# 12T_GAUGE_INPUT.net
KiCad netlist of a schematic drawn in EAGLE
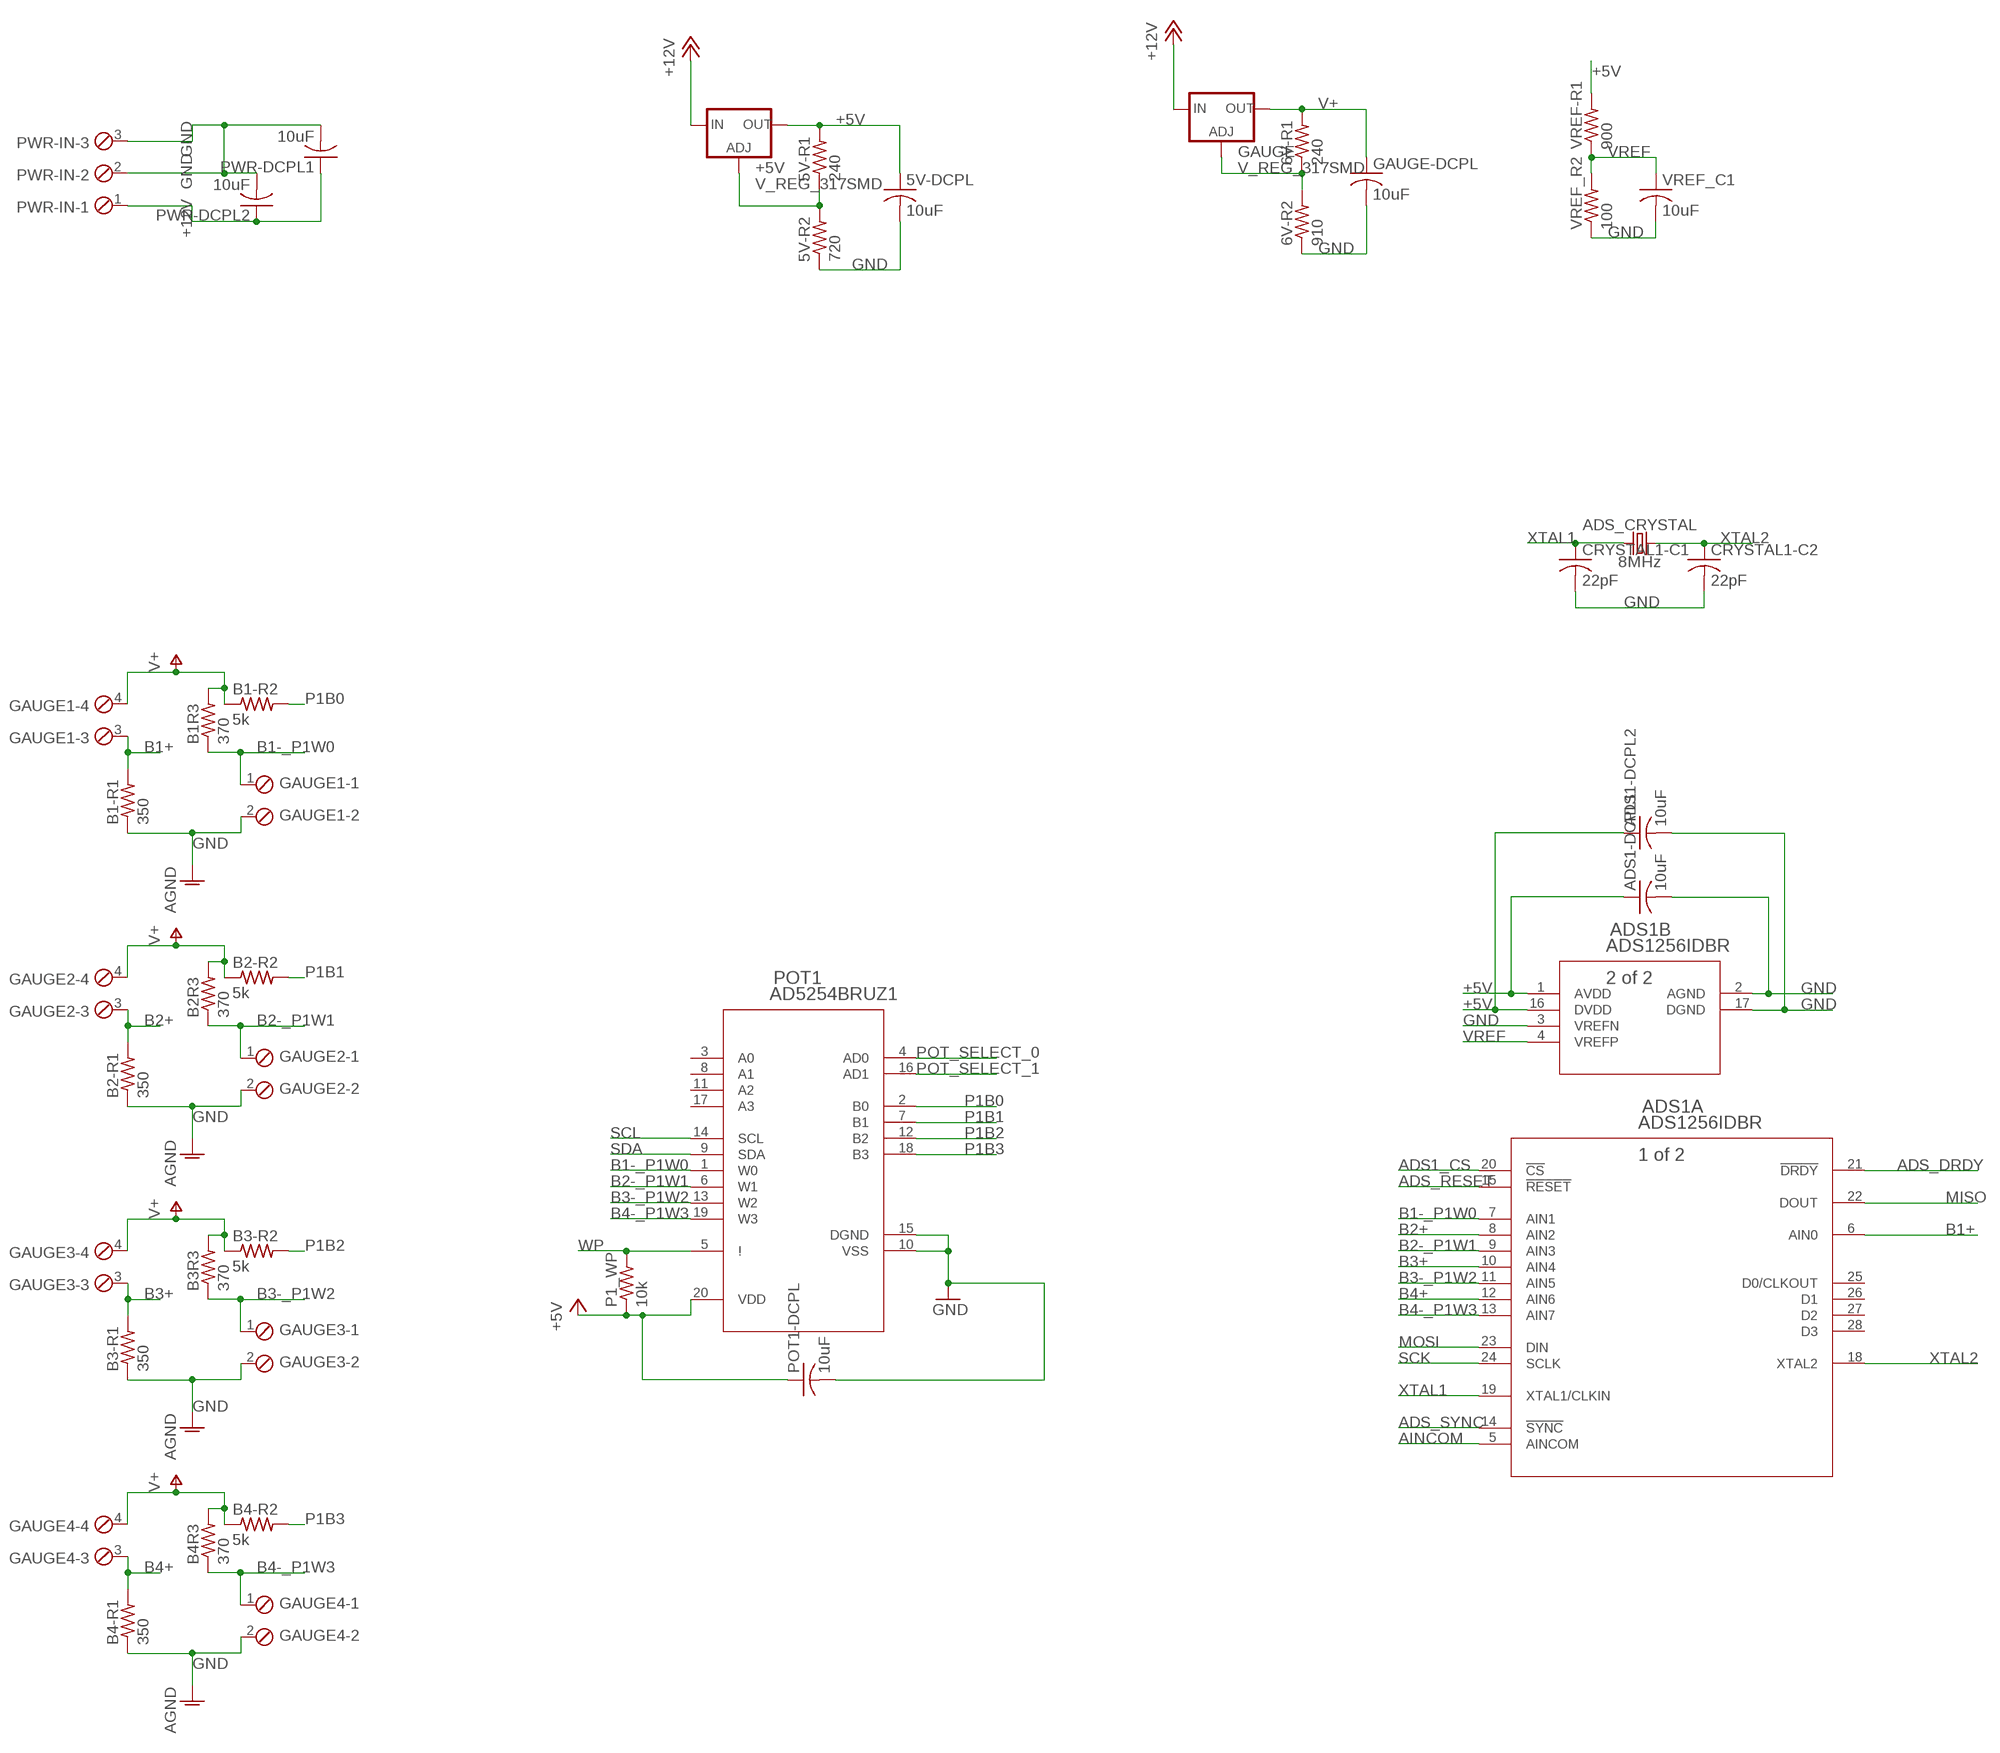
[diagram p0: schematic, sheet 1, part 1 of 3]
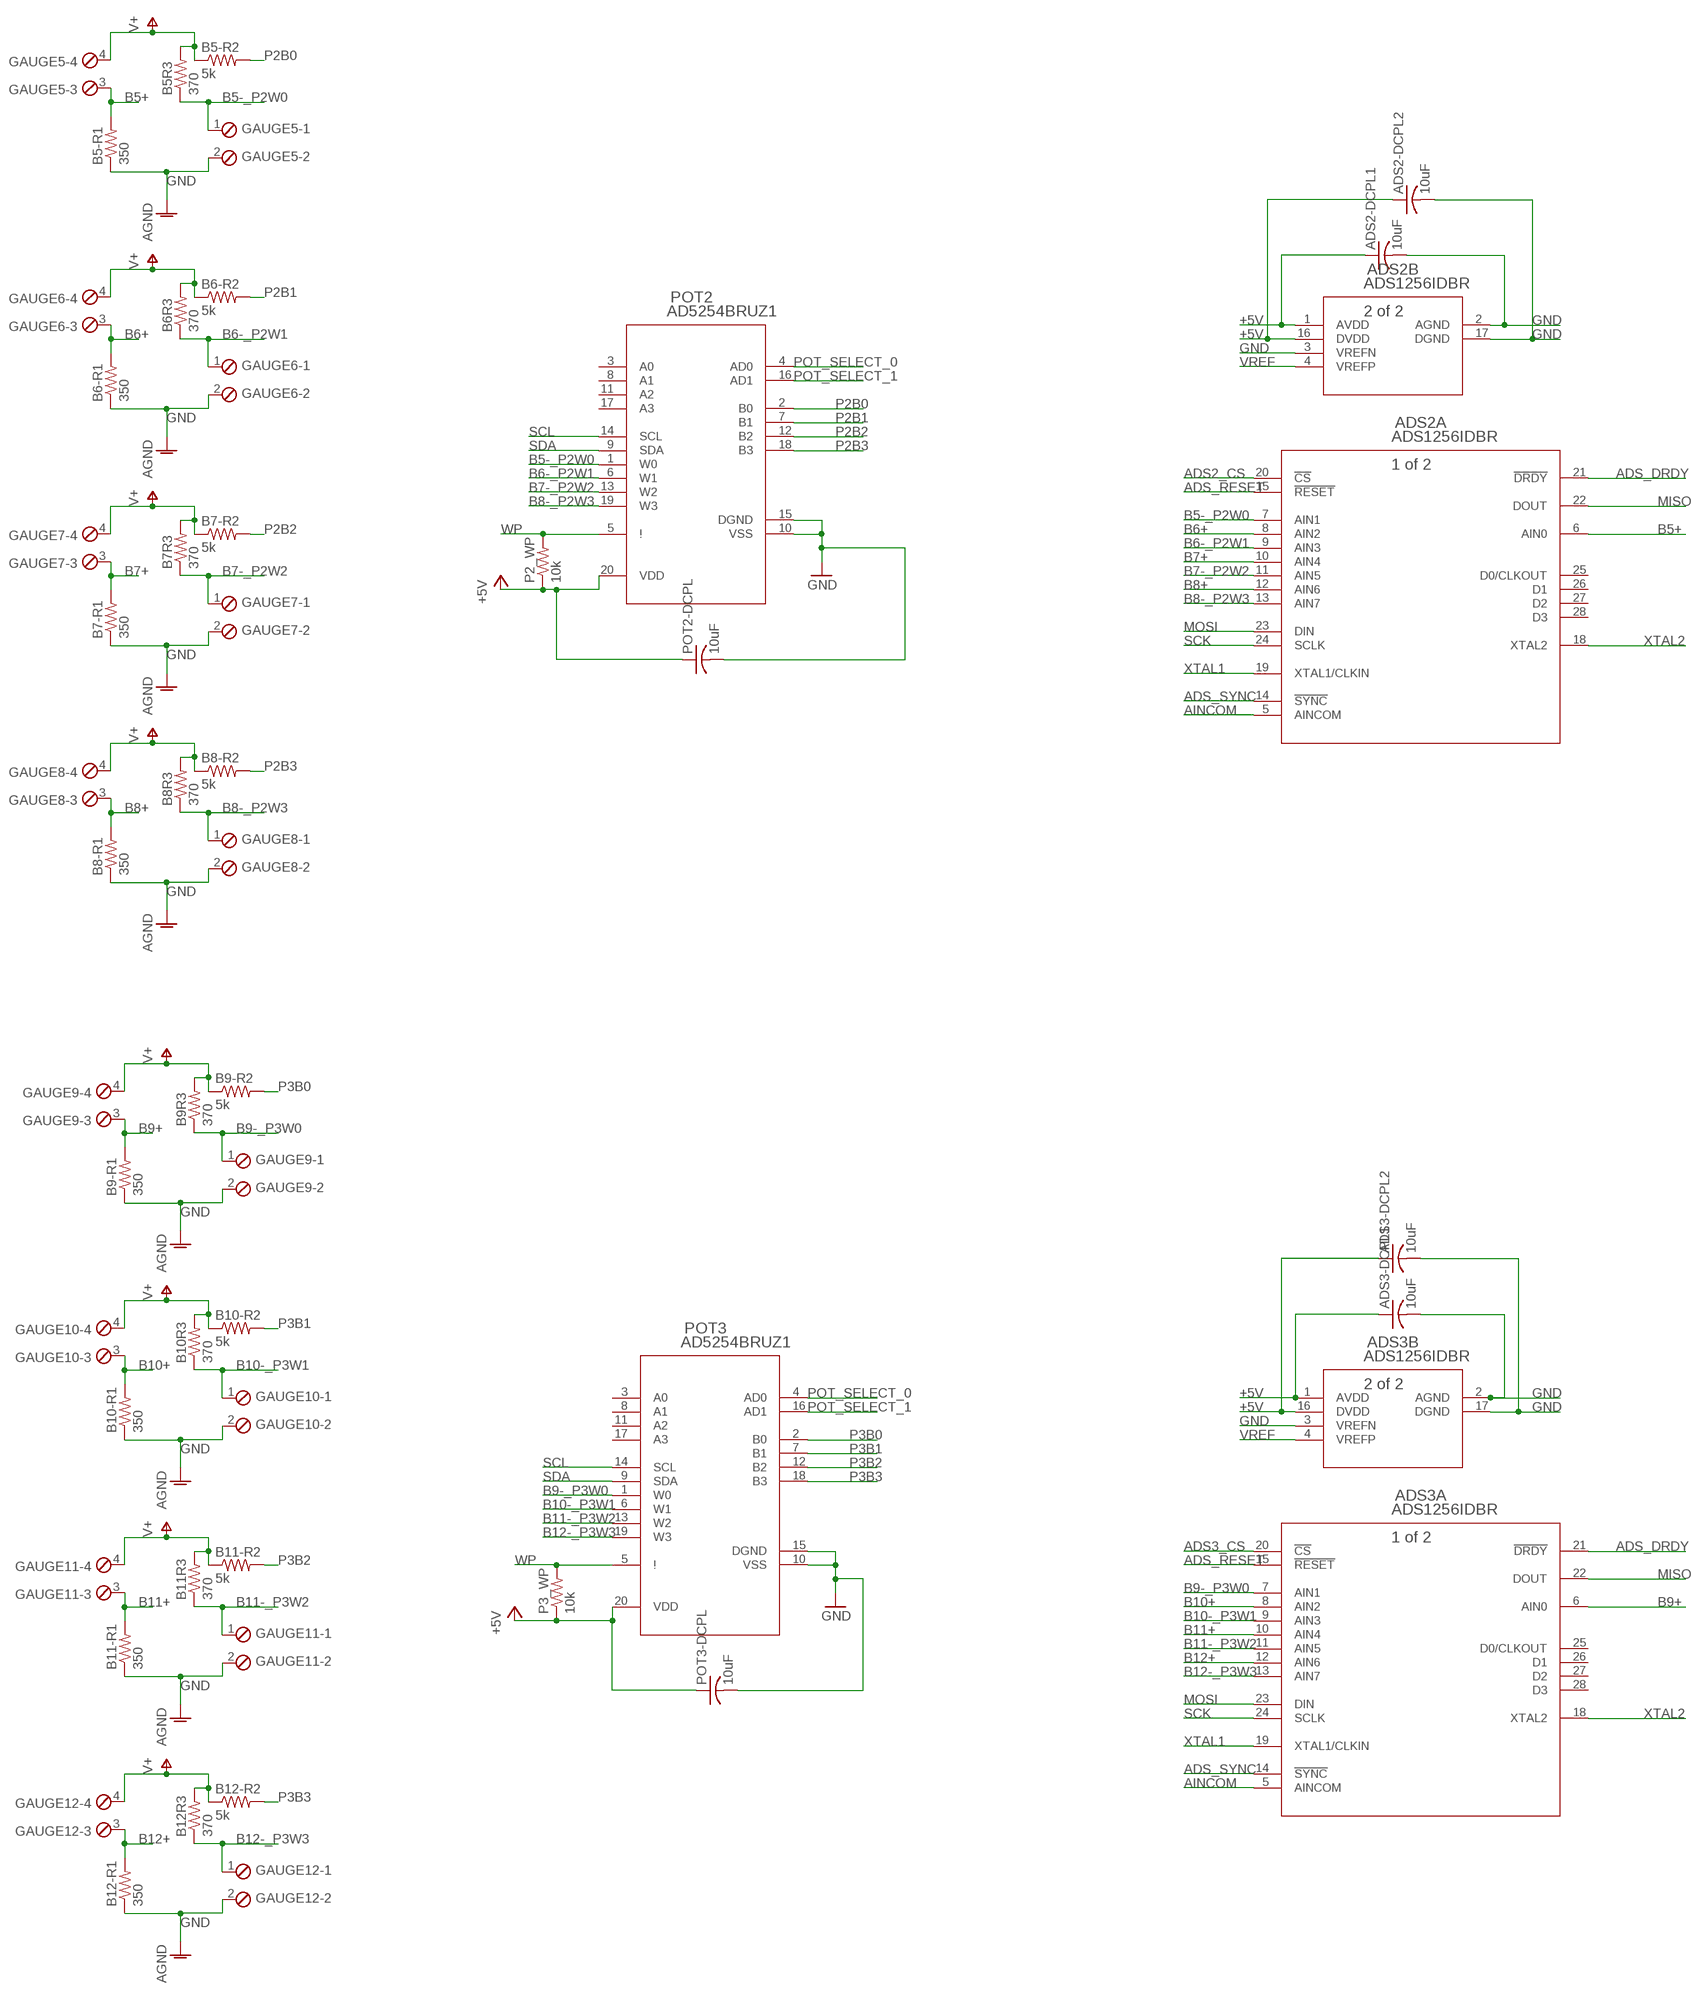
[diagram p1: schematic, sheet 1, part 2 of 3]
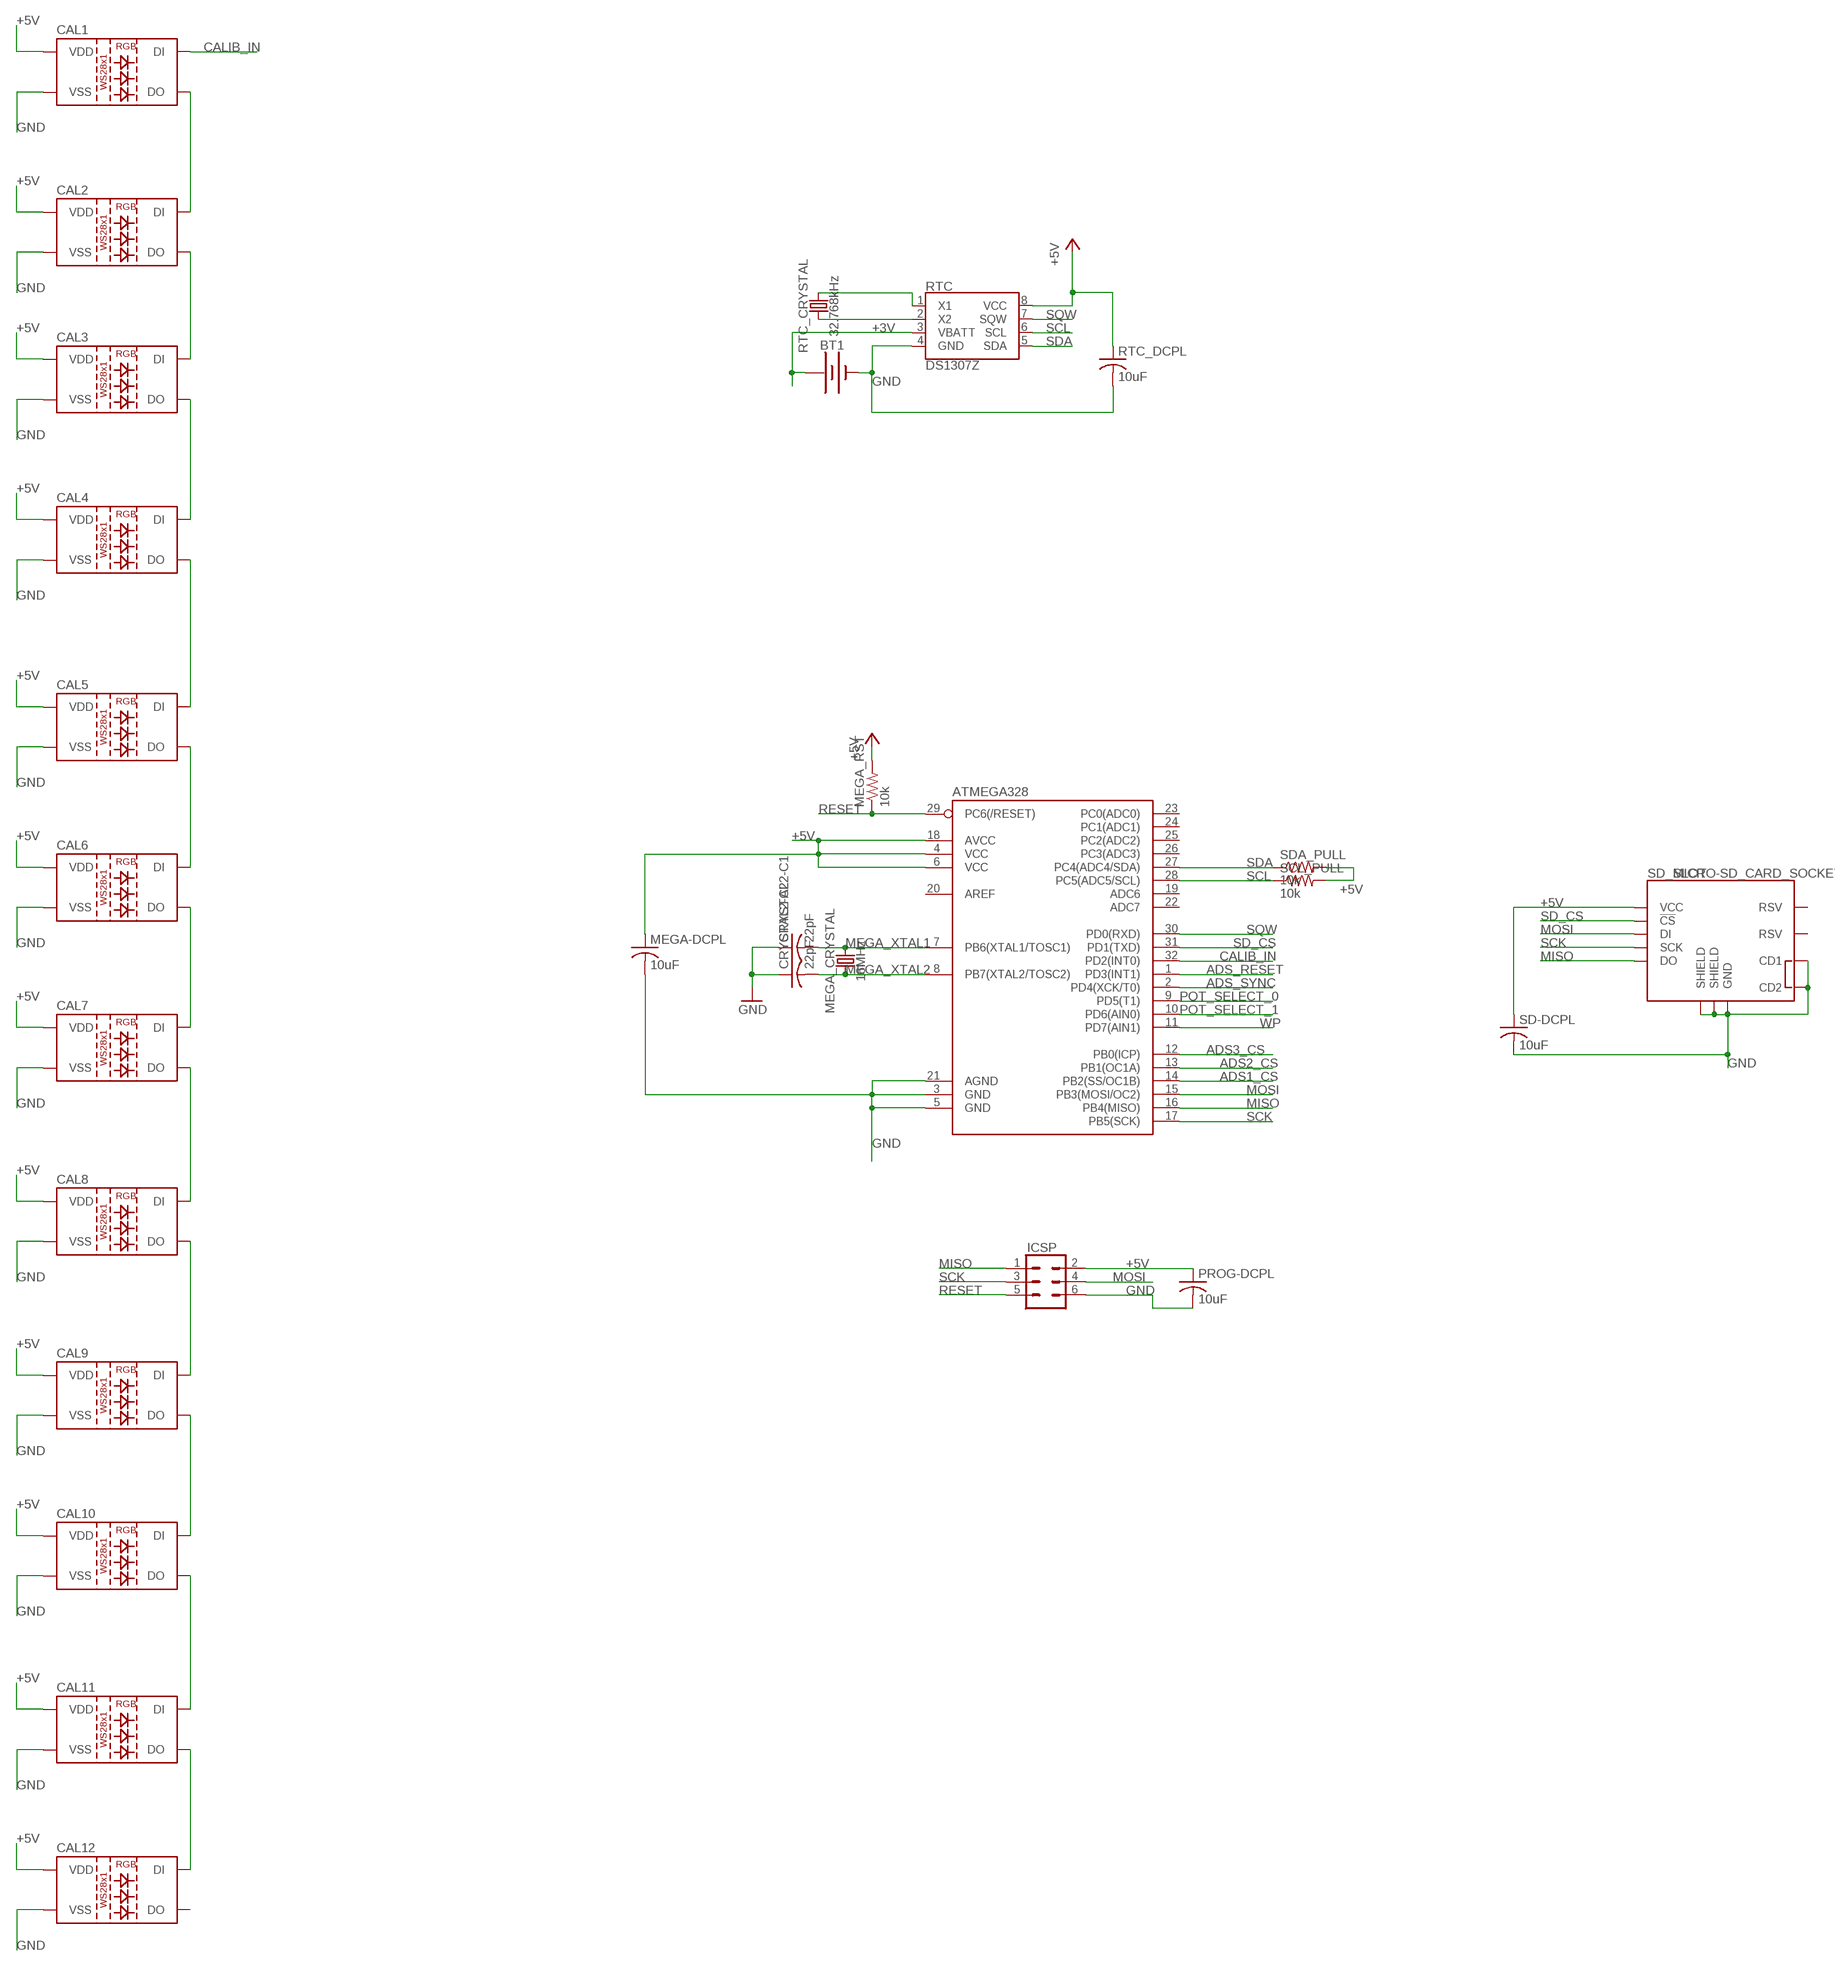
[diagram p2: schematic, sheet 1, part 3 of 3]

(export (version "E")
  (design (tool "Eeschema 10.0.6"))
  (components
    (comp (ref "+5V")
      (value "V_REG_317SMD")
      (footprint "eagle-import:SOT223")
      (libsource (lib "eagle-import") (part "V_REG_317SMD"))
    )
    (comp (ref "5V-DCPL")
      (value "10uF")
      (footprint "eagle-import:C1206")
      (libsource (lib "eagle-import") (part "C-USC1206"))
    )
    (comp (ref "5V-R1")
      (value "240")
      (footprint "eagle-import:R1206")
      (libsource (lib "eagle-import") (part "R-US_R1206"))
    )
    (comp (ref "5V-R2")
      (value "720")
      (footprint "eagle-import:R1206")
      (libsource (lib "eagle-import") (part "R-US_R1206"))
    )
    (comp (ref "6V-R1")
      (value "240")
      (footprint "eagle-import:R1206")
      (libsource (lib "eagle-import") (part "R-US_R1206"))
    )
    (comp (ref "6V-R2")
      (value "910")
      (footprint "eagle-import:R1206")
      (libsource (lib "eagle-import") (part "R-US_R1206"))
    )
    (comp (ref "ADS1")
      (value "ADS1256IDBR")
      (footprint "eagle-import:DB28")
      (libsource (lib "eagle-import") (part "ADS1256IDBR"))
    )
    (comp (ref "ADS1-DCPL1")
      (value "10uF")
      (footprint "eagle-import:C1206")
      (libsource (lib "eagle-import") (part "C-USC1206"))
    )
    (comp (ref "ADS1-DCPL2")
      (value "10uF")
      (footprint "eagle-import:C1206")
      (libsource (lib "eagle-import") (part "C-USC1206"))
    )
    (comp (ref "ADS2")
      (value "ADS1256IDBR")
      (footprint "eagle-import:DB28")
      (libsource (lib "eagle-import") (part "ADS1256IDBR"))
    )
    (comp (ref "ADS2-DCPL1")
      (value "10uF")
      (footprint "eagle-import:C1206")
      (libsource (lib "eagle-import") (part "C-USC1206"))
    )
    (comp (ref "ADS2-DCPL2")
      (value "10uF")
      (footprint "eagle-import:C1206")
      (libsource (lib "eagle-import") (part "C-USC1206"))
    )
    (comp (ref "ADS3")
      (value "ADS1256IDBR")
      (footprint "eagle-import:DB28")
      (libsource (lib "eagle-import") (part "ADS1256IDBR"))
    )
    (comp (ref "ADS3-DCPL1")
      (value "10uF")
      (footprint "eagle-import:C1206")
      (libsource (lib "eagle-import") (part "C-USC1206"))
    )
    (comp (ref "ADS3-DCPL2")
      (value "10uF")
      (footprint "eagle-import:C1206")
      (libsource (lib "eagle-import") (part "C-USC1206"))
    )
    (comp (ref "ADS_CRYSTAL")
      (value "8MHz")
      (footprint "eagle-import:CRYSTAL-SMD-5X3.2-4PAD")
      (libsource (lib "eagle-import") (part "CRYSTAL-8MHZSMD-5X3.2"))
    )
    (comp (ref "ATMEGA328")
      (value "ATMEGA328P_TQFP")
      (footprint "eagle-import:TQFP32-08")
      (libsource (lib "eagle-import") (part "ATMEGA328P_TQFP"))
    )
    (comp (ref "B1-R1")
      (value "350")
      (footprint "eagle-import:R1206")
      (libsource (lib "eagle-import") (part "R-US_R1206"))
    )
    (comp (ref "B1-R2")
      (value "5k")
      (footprint "eagle-import:R1206")
      (libsource (lib "eagle-import") (part "R-US_R1206"))
    )
    (comp (ref "B1R3")
      (value "370")
      (footprint "eagle-import:R1206")
      (libsource (lib "eagle-import") (part "R-US_R1206"))
    )
    (comp (ref "B2-R1")
      (value "350")
      (footprint "eagle-import:R1206")
      (libsource (lib "eagle-import") (part "R-US_R1206"))
    )
    (comp (ref "B2-R2")
      (value "5k")
      (footprint "eagle-import:R1206")
      (libsource (lib "eagle-import") (part "R-US_R1206"))
    )
    (comp (ref "B2R3")
      (value "370")
      (footprint "eagle-import:R1206")
      (libsource (lib "eagle-import") (part "R-US_R1206"))
    )
    (comp (ref "B3-R1")
      (value "350")
      (footprint "eagle-import:R1206")
      (libsource (lib "eagle-import") (part "R-US_R1206"))
    )
    (comp (ref "B3-R2")
      (value "5k")
      (footprint "eagle-import:R1206")
      (libsource (lib "eagle-import") (part "R-US_R1206"))
    )
    (comp (ref "B3R3")
      (value "370")
      (footprint "eagle-import:R1206")
      (libsource (lib "eagle-import") (part "R-US_R1206"))
    )
    (comp (ref "B4-R1")
      (value "350")
      (footprint "eagle-import:R1206")
      (libsource (lib "eagle-import") (part "R-US_R1206"))
    )
    (comp (ref "B4-R2")
      (value "5k")
      (footprint "eagle-import:R1206")
      (libsource (lib "eagle-import") (part "R-US_R1206"))
    )
    (comp (ref "B4R3")
      (value "370")
      (footprint "eagle-import:R1206")
      (libsource (lib "eagle-import") (part "R-US_R1206"))
    )
    (comp (ref "B5-R1")
      (value "350")
      (footprint "eagle-import:R1206")
      (libsource (lib "eagle-import") (part "R-US_R1206"))
    )
    (comp (ref "B5-R2")
      (value "5k")
      (footprint "eagle-import:R1206")
      (libsource (lib "eagle-import") (part "R-US_R1206"))
    )
    (comp (ref "B5R3")
      (value "370")
      (footprint "eagle-import:R1206")
      (libsource (lib "eagle-import") (part "R-US_R1206"))
    )
    (comp (ref "B6-R1")
      (value "350")
      (footprint "eagle-import:R1206")
      (libsource (lib "eagle-import") (part "R-US_R1206"))
    )
    (comp (ref "B6-R2")
      (value "5k")
      (footprint "eagle-import:R1206")
      (libsource (lib "eagle-import") (part "R-US_R1206"))
    )
    (comp (ref "B6R3")
      (value "370")
      (footprint "eagle-import:R1206")
      (libsource (lib "eagle-import") (part "R-US_R1206"))
    )
    (comp (ref "B7-R1")
      (value "350")
      (footprint "eagle-import:R1206")
      (libsource (lib "eagle-import") (part "R-US_R1206"))
    )
    (comp (ref "B7-R2")
      (value "5k")
      (footprint "eagle-import:R1206")
      (libsource (lib "eagle-import") (part "R-US_R1206"))
    )
    (comp (ref "B7R3")
      (value "370")
      (footprint "eagle-import:R1206")
      (libsource (lib "eagle-import") (part "R-US_R1206"))
    )
    (comp (ref "B8-R1")
      (value "350")
      (footprint "eagle-import:R1206")
      (libsource (lib "eagle-import") (part "R-US_R1206"))
    )
    (comp (ref "B8-R2")
      (value "5k")
      (footprint "eagle-import:R1206")
      (libsource (lib "eagle-import") (part "R-US_R1206"))
    )
    (comp (ref "B8R3")
      (value "370")
      (footprint "eagle-import:R1206")
      (libsource (lib "eagle-import") (part "R-US_R1206"))
    )
    (comp (ref "B9-R1")
      (value "350")
      (footprint "eagle-import:R1206")
      (libsource (lib "eagle-import") (part "R-US_R1206"))
    )
    (comp (ref "B9-R2")
      (value "5k")
      (footprint "eagle-import:R1206")
      (libsource (lib "eagle-import") (part "R-US_R1206"))
    )
    (comp (ref "B9R3")
      (value "370")
      (footprint "eagle-import:R1206")
      (libsource (lib "eagle-import") (part "R-US_R1206"))
    )
    (comp (ref "B10-R1")
      (value "350")
      (footprint "eagle-import:R1206")
      (libsource (lib "eagle-import") (part "R-US_R1206"))
    )
    (comp (ref "B10-R2")
      (value "5k")
      (footprint "eagle-import:R1206")
      (libsource (lib "eagle-import") (part "R-US_R1206"))
    )
    (comp (ref "B10R3")
      (value "370")
      (footprint "eagle-import:R1206")
      (libsource (lib "eagle-import") (part "R-US_R1206"))
    )
    (comp (ref "B11-R1")
      (value "350")
      (footprint "eagle-import:R1206")
      (libsource (lib "eagle-import") (part "R-US_R1206"))
    )
    (comp (ref "B11-R2")
      (value "5k")
      (footprint "eagle-import:R1206")
      (libsource (lib "eagle-import") (part "R-US_R1206"))
    )
    (comp (ref "B11R3")
      (value "370")
      (footprint "eagle-import:R1206")
      (libsource (lib "eagle-import") (part "R-US_R1206"))
    )
    (comp (ref "B12-R1")
      (value "350")
      (footprint "eagle-import:R1206")
      (libsource (lib "eagle-import") (part "R-US_R1206"))
    )
    (comp (ref "B12-R2")
      (value "5k")
      (footprint "eagle-import:R1206")
      (libsource (lib "eagle-import") (part "R-US_R1206"))
    )
    (comp (ref "B12R3")
      (value "370")
      (footprint "eagle-import:R1206")
      (libsource (lib "eagle-import") (part "R-US_R1206"))
    )
    (comp (ref "BT1")
      (value "BATTERY-12MM_SMD")
      (footprint "eagle-import:BATTCON_12MM")
      (libsource (lib "eagle-import") (part "BATTERY-12MM_SMD"))
    )
    (comp (ref "CAL1")
      (value "WS2812\"")
      (footprint "eagle-import:LED-TRICOLOR-5050-IC")
      (libsource (lib "eagle-import") (part "WS2812{dblquote}"))
    )
    (comp (ref "CAL2")
      (value "WS2812\"")
      (footprint "eagle-import:LED-TRICOLOR-5050-IC")
      (libsource (lib "eagle-import") (part "WS2812{dblquote}"))
    )
    (comp (ref "CAL3")
      (value "WS2812\"")
      (footprint "eagle-import:LED-TRICOLOR-5050-IC")
      (libsource (lib "eagle-import") (part "WS2812{dblquote}"))
    )
    (comp (ref "CAL4")
      (value "WS2812\"")
      (footprint "eagle-import:LED-TRICOLOR-5050-IC")
      (libsource (lib "eagle-import") (part "WS2812{dblquote}"))
    )
    (comp (ref "CAL5")
      (value "WS2812\"")
      (footprint "eagle-import:LED-TRICOLOR-5050-IC")
      (libsource (lib "eagle-import") (part "WS2812{dblquote}"))
    )
    (comp (ref "CAL6")
      (value "WS2812\"")
      (footprint "eagle-import:LED-TRICOLOR-5050-IC")
      (libsource (lib "eagle-import") (part "WS2812{dblquote}"))
    )
    (comp (ref "CAL7")
      (value "WS2812\"")
      (footprint "eagle-import:LED-TRICOLOR-5050-IC")
      (libsource (lib "eagle-import") (part "WS2812{dblquote}"))
    )
    (comp (ref "CAL8")
      (value "WS2812\"")
      (footprint "eagle-import:LED-TRICOLOR-5050-IC")
      (libsource (lib "eagle-import") (part "WS2812{dblquote}"))
    )
    (comp (ref "CAL9")
      (value "WS2812\"")
      (footprint "eagle-import:LED-TRICOLOR-5050-IC")
      (libsource (lib "eagle-import") (part "WS2812{dblquote}"))
    )
    (comp (ref "CAL10")
      (value "WS2812\"")
      (footprint "eagle-import:LED-TRICOLOR-5050-IC")
      (libsource (lib "eagle-import") (part "WS2812{dblquote}"))
    )
    (comp (ref "CAL11")
      (value "WS2812\"")
      (footprint "eagle-import:LED-TRICOLOR-5050-IC")
      (libsource (lib "eagle-import") (part "WS2812{dblquote}"))
    )
    (comp (ref "CAL12")
      (value "WS2812\"")
      (footprint "eagle-import:LED-TRICOLOR-5050-IC")
      (libsource (lib "eagle-import") (part "WS2812{dblquote}"))
    )
    (comp (ref "CRYSTAL1-C1")
      (value "22pF")
      (footprint "eagle-import:C1206")
      (libsource (lib "eagle-import") (part "C-USC1206"))
    )
    (comp (ref "CRYSTAL1-C2")
      (value "22pF")
      (footprint "eagle-import:C1206")
      (libsource (lib "eagle-import") (part "C-USC1206"))
    )
    (comp (ref "CRYSTAL2-C1")
      (value "22pF")
      (footprint "eagle-import:C1206")
      (libsource (lib "eagle-import") (part "C-USC1206"))
    )
    (comp (ref "CRYSTAL2-C2")
      (value "22pF")
      (footprint "eagle-import:C1206")
      (libsource (lib "eagle-import") (part "C-USC1206"))
    )
    (comp (ref "GAUGE")
      (value "V_REG_317SMD")
      (footprint "eagle-import:SOT223")
      (libsource (lib "eagle-import") (part "V_REG_317SMD"))
    )
    (comp (ref "GAUGE-DCPL")
      (value "10uF")
      (footprint "eagle-import:C1206")
      (libsource (lib "eagle-import") (part "C-USC1206"))
    )
    (comp (ref "GAUGE1")
      (value "MPT4")
      (footprint "eagle-import:4POL254")
      (libsource (lib "eagle-import") (part "MPT4"))
    )
    (comp (ref "GAUGE2")
      (value "MPT4")
      (footprint "eagle-import:4POL254")
      (libsource (lib "eagle-import") (part "MPT4"))
    )
    (comp (ref "GAUGE3")
      (value "MPT4")
      (footprint "eagle-import:4POL254")
      (libsource (lib "eagle-import") (part "MPT4"))
    )
    (comp (ref "GAUGE4")
      (value "MPT4")
      (footprint "eagle-import:4POL254")
      (libsource (lib "eagle-import") (part "MPT4"))
    )
    (comp (ref "GAUGE5")
      (value "MPT4")
      (footprint "eagle-import:4POL254")
      (libsource (lib "eagle-import") (part "MPT4"))
    )
    (comp (ref "GAUGE6")
      (value "MPT4")
      (footprint "eagle-import:4POL254")
      (libsource (lib "eagle-import") (part "MPT4"))
    )
    (comp (ref "GAUGE7")
      (value "MPT4")
      (footprint "eagle-import:4POL254")
      (libsource (lib "eagle-import") (part "MPT4"))
    )
    (comp (ref "GAUGE8")
      (value "MPT4")
      (footprint "eagle-import:4POL254")
      (libsource (lib "eagle-import") (part "MPT4"))
    )
    (comp (ref "GAUGE9")
      (value "MPT4")
      (footprint "eagle-import:4POL254")
      (libsource (lib "eagle-import") (part "MPT4"))
    )
    (comp (ref "GAUGE10")
      (value "MPT4")
      (footprint "eagle-import:4POL254")
      (libsource (lib "eagle-import") (part "MPT4"))
    )
    (comp (ref "GAUGE11")
      (value "MPT4")
      (footprint "eagle-import:4POL254")
      (libsource (lib "eagle-import") (part "MPT4"))
    )
    (comp (ref "GAUGE12")
      (value "MPT4")
      (footprint "eagle-import:4POL254")
      (libsource (lib "eagle-import") (part "MPT4"))
    )
    (comp (ref "ICSP")
      (value "CONN_03X2FEMALE_SMD")
      (footprint "eagle-import:2X3_SMD")
      (libsource (lib "eagle-import") (part "CONN_03X2FEMALE_SMD"))
    )
    (comp (ref "MEGA-DCPL")
      (value "10uF")
      (footprint "eagle-import:C1206")
      (libsource (lib "eagle-import") (part "C-USC1206"))
    )
    (comp (ref "MEGA_CRYSTAL")
      (value "16MHz")
      (footprint "eagle-import:CRYSTAL-SMD-5X3.2-4PAD")
      (libsource (lib "eagle-import") (part "CRYSTAL-16MHZSMD-5X3.2"))
    )
    (comp (ref "MEGA_RST")
      (value "10k")
      (footprint "eagle-import:R1206")
      (libsource (lib "eagle-import") (part "R-US_R1206"))
    )
    (comp (ref "P1_WP")
      (value "10k")
      (footprint "eagle-import:R1206")
      (libsource (lib "eagle-import") (part "R-US_R1206"))
    )
    (comp (ref "P2_WP")
      (value "10k")
      (footprint "eagle-import:R1206")
      (libsource (lib "eagle-import") (part "R-US_R1206"))
    )
    (comp (ref "P3_WP")
      (value "10k")
      (footprint "eagle-import:R1206")
      (libsource (lib "eagle-import") (part "R-US_R1206"))
    )
    (comp (ref "POT1")
      (value "AD5254BRUZ1")
      (footprint "eagle-import:RU_20")
      (libsource (lib "eagle-import") (part "AD5254BRUZ1"))
    )
    (comp (ref "POT1-DCPL")
      (value "10uF")
      (footprint "eagle-import:C1206")
      (libsource (lib "eagle-import") (part "C-USC1206"))
    )
    (comp (ref "POT2")
      (value "AD5254BRUZ1")
      (footprint "eagle-import:RU_20")
      (libsource (lib "eagle-import") (part "AD5254BRUZ1"))
    )
    (comp (ref "POT2-DCPL")
      (value "10uF")
      (footprint "eagle-import:C1206")
      (libsource (lib "eagle-import") (part "C-USC1206"))
    )
    (comp (ref "POT3")
      (value "AD5254BRUZ1")
      (footprint "eagle-import:RU_20")
      (libsource (lib "eagle-import") (part "AD5254BRUZ1"))
    )
    (comp (ref "POT3-DCPL")
      (value "10uF")
      (footprint "eagle-import:C1206")
      (libsource (lib "eagle-import") (part "C-USC1206"))
    )
    (comp (ref "PROG-DCPL")
      (value "10uF")
      (footprint "eagle-import:C1206")
      (libsource (lib "eagle-import") (part "C-USC1206"))
    )
    (comp (ref "PWR-DCPL1")
      (value "10uF")
      (footprint "eagle-import:C1206")
      (libsource (lib "eagle-import") (part "C-USC1206"))
    )
    (comp (ref "PWR-DCPL2")
      (value "10uF")
      (footprint "eagle-import:C1206")
      (libsource (lib "eagle-import") (part "C-USC1206"))
    )
    (comp (ref "PWR-IN")
      (value "MPT3")
      (footprint "eagle-import:3POL254")
      (libsource (lib "eagle-import") (part "MPT3"))
    )
    (comp (ref "RTC")
      (value "DS1307Z")
      (footprint "eagle-import:SO08-0.15")
      (libsource (lib "eagle-import") (part "DS1307Z"))
    )
    (comp (ref "RTC_CRYSTAL")
      (value "32.768kHz")
      (footprint "eagle-import:CRYSTAL-SMD-3.2X1.5MM")
      (libsource (lib "eagle-import") (part "CRYSTAL-32.768KHZSMD-3.2X1.5"))
    )
    (comp (ref "RTC_DCPL")
      (value "10uF")
      (footprint "eagle-import:C1206")
      (libsource (lib "eagle-import") (part "C-USC1206"))
    )
    (comp (ref "SCL_PULL")
      (value "10k")
      (footprint "eagle-import:R1206")
      (libsource (lib "eagle-import") (part "R-US_R1206"))
    )
    (comp (ref "SD-DCPL")
      (value "10uF")
      (footprint "eagle-import:C1206")
      (libsource (lib "eagle-import") (part "C-USC1206"))
    )
    (comp (ref "SDA_PULL")
      (value "10k")
      (footprint "eagle-import:R1206")
      (libsource (lib "eagle-import") (part "R-US_R1206"))
    )
    (comp (ref "SD_SLOT")
      (value "MICRO-SD_CARD_SOCKET")
      (footprint "eagle-import:MICRO-SD-SOCKET")
      (libsource (lib "eagle-import") (part "MICRO-SD_CARD_SOCKET"))
    )
    (comp (ref "VREF-R1")
      (value "900")
      (footprint "eagle-import:R1206")
      (libsource (lib "eagle-import") (part "R-US_R1206"))
    )
    (comp (ref "VREF_C1")
      (value "10uF")
      (footprint "eagle-import:C1206")
      (libsource (lib "eagle-import") (part "C-USC1206"))
    )
    (comp (ref "VREF_R2")
      (value "100")
      (footprint "eagle-import:R1206")
      (libsource (lib "eagle-import") (part "R-US_R1206"))
    )
  )
  (nets
    (net (code "1") (name "+5V") (class "Default")
      (node (ref "+5V") (pin "2") (pinfunction "OUT_2") (pintype "output"))
      (node (ref "5V-DCPL") (pin "1") (pinfunction "1_1") (pintype "passive"))
      (node (ref "5V-R1") (pin "2") (pinfunction "2_2") (pintype "passive"))
      (node (ref "ADS1") (pin "1") (pinfunction "AVDD_1") (pintype "passive"))
      (node (ref "ADS1") (pin "16") (pinfunction "DVDD_16") (pintype "power_in"))
      (node (ref "ADS1-DCPL1") (pin "1") (pinfunction "1_1") (pintype "passive"))
      (node (ref "ADS1-DCPL2") (pin "1") (pinfunction "1_1") (pintype "passive"))
      (node (ref "ADS2") (pin "1") (pinfunction "AVDD_1") (pintype "passive"))
      (node (ref "ADS2") (pin "16") (pinfunction "DVDD_16") (pintype "power_in"))
      (node (ref "ADS2-DCPL1") (pin "1") (pinfunction "1_1") (pintype "passive"))
      (node (ref "ADS2-DCPL2") (pin "1") (pinfunction "1_1") (pintype "passive"))
      (node (ref "ADS3") (pin "1") (pinfunction "AVDD_1") (pintype "passive"))
      (node (ref "ADS3") (pin "16") (pinfunction "DVDD_16") (pintype "power_in"))
      (node (ref "ADS3-DCPL1") (pin "1") (pinfunction "1_1") (pintype "passive"))
      (node (ref "ADS3-DCPL2") (pin "1") (pinfunction "1_1") (pintype "passive"))
      (node (ref "ATMEGA328") (pin "18") (pinfunction "AVCC_18") (pintype "bidirectional"))
      (node (ref "ATMEGA328") (pin "4") (pinfunction "VCC_4") (pintype "bidirectional"))
      (node (ref "ATMEGA328") (pin "6") (pinfunction "VCC_6") (pintype "bidirectional"))
      (node (ref "CAL1") (pin "3") (pinfunction "VDD_3") (pintype "bidirectional"))
      (node (ref "CAL1") (pin "5") (pinfunction "VDD_5") (pintype "bidirectional"))
      (node (ref "CAL10") (pin "3") (pinfunction "VDD_3") (pintype "bidirectional"))
      (node (ref "CAL10") (pin "5") (pinfunction "VDD_5") (pintype "bidirectional"))
      (node (ref "CAL11") (pin "3") (pinfunction "VDD_3") (pintype "bidirectional"))
      (node (ref "CAL11") (pin "5") (pinfunction "VDD_5") (pintype "bidirectional"))
      (node (ref "CAL12") (pin "3") (pinfunction "VDD_3") (pintype "bidirectional"))
      (node (ref "CAL12") (pin "5") (pinfunction "VDD_5") (pintype "bidirectional"))
      (node (ref "CAL2") (pin "3") (pinfunction "VDD_3") (pintype "bidirectional"))
      (node (ref "CAL2") (pin "5") (pinfunction "VDD_5") (pintype "bidirectional"))
      (node (ref "CAL3") (pin "3") (pinfunction "VDD_3") (pintype "bidirectional"))
      (node (ref "CAL3") (pin "5") (pinfunction "VDD_5") (pintype "bidirectional"))
      (node (ref "CAL4") (pin "3") (pinfunction "VDD_3") (pintype "bidirectional"))
      (node (ref "CAL4") (pin "5") (pinfunction "VDD_5") (pintype "bidirectional"))
      (node (ref "CAL5") (pin "3") (pinfunction "VDD_3") (pintype "bidirectional"))
      (node (ref "CAL5") (pin "5") (pinfunction "VDD_5") (pintype "bidirectional"))
      (node (ref "CAL6") (pin "3") (pinfunction "VDD_3") (pintype "bidirectional"))
      (node (ref "CAL6") (pin "5") (pinfunction "VDD_5") (pintype "bidirectional"))
      (node (ref "CAL7") (pin "3") (pinfunction "VDD_3") (pintype "bidirectional"))
      (node (ref "CAL7") (pin "5") (pinfunction "VDD_5") (pintype "bidirectional"))
      (node (ref "CAL8") (pin "3") (pinfunction "VDD_3") (pintype "bidirectional"))
      (node (ref "CAL8") (pin "5") (pinfunction "VDD_5") (pintype "bidirectional"))
      (node (ref "CAL9") (pin "3") (pinfunction "VDD_3") (pintype "bidirectional"))
      (node (ref "CAL9") (pin "5") (pinfunction "VDD_5") (pintype "bidirectional"))
      (node (ref "ICSP") (pin "2") (pinfunction "2_2") (pintype "bidirectional"))
      (node (ref "MEGA-DCPL") (pin "1") (pinfunction "1_1") (pintype "passive"))
      (node (ref "MEGA_RST") (pin "2") (pinfunction "2_2") (pintype "passive"))
      (node (ref "P1_WP") (pin "1") (pinfunction "1_1") (pintype "passive"))
      (node (ref "P2_WP") (pin "1") (pinfunction "1_1") (pintype "passive"))
      (node (ref "P3_WP") (pin "1") (pinfunction "1_1") (pintype "passive"))
      (node (ref "POT1") (pin "20") (pinfunction "VDD_20") (pintype "power_in"))
      (node (ref "POT1-DCPL") (pin "1") (pinfunction "1_1") (pintype "passive"))
      (node (ref "POT2") (pin "20") (pinfunction "VDD_20") (pintype "power_in"))
      (node (ref "POT2-DCPL") (pin "1") (pinfunction "1_1") (pintype "passive"))
      (node (ref "POT3") (pin "20") (pinfunction "VDD_20") (pintype "power_in"))
      (node (ref "POT3-DCPL") (pin "1") (pinfunction "1_1") (pintype "passive"))
      (node (ref "PROG-DCPL") (pin "1") (pinfunction "1_1") (pintype "passive"))
      (node (ref "RTC") (pin "8") (pinfunction "VCC_8") (pintype "bidirectional"))
      (node (ref "RTC_DCPL") (pin "1") (pinfunction "1_1") (pintype "passive"))
      (node (ref "SCL_PULL") (pin "2") (pinfunction "2_2") (pintype "passive"))
      (node (ref "SD-DCPL") (pin "1") (pinfunction "1_1") (pintype "passive"))
      (node (ref "SDA_PULL") (pin "2") (pinfunction "2_2") (pintype "passive"))
      (node (ref "SD_SLOT") (pin "VCC") (pinfunction "VCC_VCC") (pintype "bidirectional"))
      (node (ref "VREF-R1") (pin "2") (pinfunction "2_2") (pintype "passive"))
    )
    (net (code "2") (name "+12V") (class "Default")
      (node (ref "+5V") (pin "3") (pinfunction "IN_3") (pintype "input"))
      (node (ref "GAUGE") (pin "3") (pinfunction "IN_3") (pintype "input"))
      (node (ref "PWR-DCPL1") (pin "1") (pinfunction "1_1") (pintype "passive"))
      (node (ref "PWR-DCPL2") (pin "1") (pinfunction "1_1") (pintype "passive"))
      (node (ref "PWR-IN") (pin "1") (pinfunction "1_1") (pintype "passive"))
    )
    (net (code "3") (name "/+3V") (class "Default")
      (node (ref "BT1") (pin "PWR@1") (pinfunction "+_PWR@1") (pintype "power_in"))
      (node (ref "RTC") (pin "3") (pinfunction "VBATT_3") (pintype "bidirectional"))
    )
    (net (code "4") (name "/ADS1_CS") (class "Default")
      (node (ref "ADS1") (pin "20") (pinfunction "~{CS}_20") (pintype "input"))
      (node (ref "ATMEGA328") (pin "14") (pinfunction "PB2(SS/OC1B)_14") (pintype "bidirectional"))
    )
    (net (code "5") (name "/ADS2_CS") (class "Default")
      (node (ref "ADS2") (pin "20") (pinfunction "~{CS}_20") (pintype "input"))
      (node (ref "ATMEGA328") (pin "13") (pinfunction "PB1(OC1A)_13") (pintype "bidirectional"))
    )
    (net (code "6") (name "/ADS3_CS") (class "Default")
      (node (ref "ADS3") (pin "20") (pinfunction "~{CS}_20") (pintype "input"))
      (node (ref "ATMEGA328") (pin "12") (pinfunction "PB0(ICP)_12") (pintype "bidirectional"))
    )
    (net (code "7") (name "/ADS_DRDY") (class "Default")
      (node (ref "ADS1") (pin "21") (pinfunction "~{DRDY}_21") (pintype "output"))
      (node (ref "ADS2") (pin "21") (pinfunction "~{DRDY}_21") (pintype "output"))
      (node (ref "ADS3") (pin "21") (pinfunction "~{DRDY}_21") (pintype "output"))
    )
    (net (code "8") (name "/ADS_RESET") (class "Default")
      (node (ref "ADS1") (pin "15") (pinfunction "~{RESET}_15") (pintype "input"))
      (node (ref "ADS2") (pin "15") (pinfunction "~{RESET}_15") (pintype "input"))
      (node (ref "ADS3") (pin "15") (pinfunction "~{RESET}_15") (pintype "input"))
      (node (ref "ATMEGA328") (pin "1") (pinfunction "PD3(INT1)_1") (pintype "bidirectional"))
    )
    (net (code "9") (name "/ADS_SYNC") (class "Default")
      (node (ref "ADS1") (pin "14") (pinfunction "~{SYNC}_14") (pintype "passive"))
      (node (ref "ADS2") (pin "14") (pinfunction "~{SYNC}_14") (pintype "passive"))
      (node (ref "ADS3") (pin "14") (pinfunction "~{SYNC}_14") (pintype "passive"))
      (node (ref "ATMEGA328") (pin "2") (pinfunction "PD4(XCK/T0)_2") (pintype "bidirectional"))
    )
    (net (code "10") (name "/AINCOM") (class "Default")
      (node (ref "ADS1") (pin "5") (pinfunction "AINCOM_5") (pintype "passive"))
      (node (ref "ADS2") (pin "5") (pinfunction "AINCOM_5") (pintype "passive"))
      (node (ref "ADS3") (pin "5") (pinfunction "AINCOM_5") (pintype "passive"))
    )
    (net (code "11") (name "/B1+") (class "Default")
      (node (ref "ADS1") (pin "6") (pinfunction "AIN0_6") (pintype "passive"))
      (node (ref "B1-R1") (pin "2") (pinfunction "2_2") (pintype "passive"))
      (node (ref "GAUGE1") (pin "3") (pinfunction "1_3") (pintype "passive"))
    )
    (net (code "12") (name "/B1-_P1W0") (class "Default")
      (node (ref "ADS1") (pin "7") (pinfunction "AIN1_7") (pintype "passive"))
      (node (ref "B1R3") (pin "1") (pinfunction "1_1") (pintype "passive"))
      (node (ref "GAUGE1") (pin "1") (pinfunction "1_1") (pintype "passive"))
      (node (ref "POT1") (pin "1") (pinfunction "W0_1") (pintype "passive"))
    )
    (net (code "13") (name "/B2+") (class "Default")
      (node (ref "ADS1") (pin "8") (pinfunction "AIN2_8") (pintype "passive"))
      (node (ref "B2-R1") (pin "2") (pinfunction "2_2") (pintype "passive"))
      (node (ref "GAUGE2") (pin "3") (pinfunction "1_3") (pintype "passive"))
    )
    (net (code "14") (name "/B2-_P1W1") (class "Default")
      (node (ref "ADS1") (pin "9") (pinfunction "AIN3_9") (pintype "passive"))
      (node (ref "B2R3") (pin "1") (pinfunction "1_1") (pintype "passive"))
      (node (ref "GAUGE2") (pin "1") (pinfunction "1_1") (pintype "passive"))
      (node (ref "POT1") (pin "6") (pinfunction "W1_6") (pintype "passive"))
    )
    (net (code "15") (name "/B3+") (class "Default")
      (node (ref "ADS1") (pin "10") (pinfunction "AIN4_10") (pintype "passive"))
      (node (ref "B3-R1") (pin "2") (pinfunction "2_2") (pintype "passive"))
      (node (ref "GAUGE3") (pin "3") (pinfunction "1_3") (pintype "passive"))
    )
    (net (code "16") (name "/B3-_P1W2") (class "Default")
      (node (ref "ADS1") (pin "11") (pinfunction "AIN5_11") (pintype "passive"))
      (node (ref "B3R3") (pin "1") (pinfunction "1_1") (pintype "passive"))
      (node (ref "GAUGE3") (pin "1") (pinfunction "1_1") (pintype "passive"))
      (node (ref "POT1") (pin "13") (pinfunction "W2_13") (pintype "passive"))
    )
    (net (code "17") (name "/B4+") (class "Default")
      (node (ref "ADS1") (pin "12") (pinfunction "AIN6_12") (pintype "passive"))
      (node (ref "B4-R1") (pin "2") (pinfunction "2_2") (pintype "passive"))
      (node (ref "GAUGE4") (pin "3") (pinfunction "1_3") (pintype "passive"))
    )
    (net (code "18") (name "/B4-_P1W3") (class "Default")
      (node (ref "ADS1") (pin "13") (pinfunction "AIN7_13") (pintype "passive"))
      (node (ref "B4R3") (pin "1") (pinfunction "1_1") (pintype "passive"))
      (node (ref "GAUGE4") (pin "1") (pinfunction "1_1") (pintype "passive"))
      (node (ref "POT1") (pin "19") (pinfunction "W3_19") (pintype "passive"))
    )
    (net (code "19") (name "/B5+") (class "Default")
      (node (ref "ADS2") (pin "6") (pinfunction "AIN0_6") (pintype "passive"))
      (node (ref "B5-R1") (pin "2") (pinfunction "2_2") (pintype "passive"))
      (node (ref "GAUGE5") (pin "3") (pinfunction "1_3") (pintype "passive"))
    )
    (net (code "20") (name "/B5-_P2W0") (class "Default")
      (node (ref "ADS2") (pin "7") (pinfunction "AIN1_7") (pintype "passive"))
      (node (ref "B5R3") (pin "1") (pinfunction "1_1") (pintype "passive"))
      (node (ref "GAUGE5") (pin "1") (pinfunction "1_1") (pintype "passive"))
      (node (ref "POT2") (pin "1") (pinfunction "W0_1") (pintype "passive"))
    )
    (net (code "21") (name "/B6+") (class "Default")
      (node (ref "ADS2") (pin "8") (pinfunction "AIN2_8") (pintype "passive"))
      (node (ref "B6-R1") (pin "2") (pinfunction "2_2") (pintype "passive"))
      (node (ref "GAUGE6") (pin "3") (pinfunction "1_3") (pintype "passive"))
    )
    (net (code "22") (name "/B6-_P2W1") (class "Default")
      (node (ref "ADS2") (pin "9") (pinfunction "AIN3_9") (pintype "passive"))
      (node (ref "B6R3") (pin "1") (pinfunction "1_1") (pintype "passive"))
      (node (ref "GAUGE6") (pin "1") (pinfunction "1_1") (pintype "passive"))
      (node (ref "POT2") (pin "6") (pinfunction "W1_6") (pintype "passive"))
    )
    (net (code "23") (name "/B7+") (class "Default")
      (node (ref "ADS2") (pin "10") (pinfunction "AIN4_10") (pintype "passive"))
      (node (ref "B7-R1") (pin "2") (pinfunction "2_2") (pintype "passive"))
      (node (ref "GAUGE7") (pin "3") (pinfunction "1_3") (pintype "passive"))
    )
    (net (code "24") (name "/B7-_P2W2") (class "Default")
      (node (ref "ADS2") (pin "11") (pinfunction "AIN5_11") (pintype "passive"))
      (node (ref "B7R3") (pin "1") (pinfunction "1_1") (pintype "passive"))
      (node (ref "GAUGE7") (pin "1") (pinfunction "1_1") (pintype "passive"))
      (node (ref "POT2") (pin "13") (pinfunction "W2_13") (pintype "passive"))
    )
    (net (code "25") (name "/B8+") (class "Default")
      (node (ref "ADS2") (pin "12") (pinfunction "AIN6_12") (pintype "passive"))
      (node (ref "B8-R1") (pin "2") (pinfunction "2_2") (pintype "passive"))
      (node (ref "GAUGE8") (pin "3") (pinfunction "1_3") (pintype "passive"))
    )
    (net (code "26") (name "/B8-_P2W3") (class "Default")
      (node (ref "ADS2") (pin "13") (pinfunction "AIN7_13") (pintype "passive"))
      (node (ref "B8R3") (pin "1") (pinfunction "1_1") (pintype "passive"))
      (node (ref "GAUGE8") (pin "1") (pinfunction "1_1") (pintype "passive"))
      (node (ref "POT2") (pin "19") (pinfunction "W3_19") (pintype "passive"))
    )
    (net (code "27") (name "/B9+") (class "Default")
      (node (ref "ADS3") (pin "6") (pinfunction "AIN0_6") (pintype "passive"))
      (node (ref "B9-R1") (pin "2") (pinfunction "2_2") (pintype "passive"))
      (node (ref "GAUGE9") (pin "3") (pinfunction "1_3") (pintype "passive"))
    )
    (net (code "28") (name "/B9-_P3W0") (class "Default")
      (node (ref "ADS3") (pin "7") (pinfunction "AIN1_7") (pintype "passive"))
      (node (ref "B9R3") (pin "1") (pinfunction "1_1") (pintype "passive"))
      (node (ref "GAUGE9") (pin "1") (pinfunction "1_1") (pintype "passive"))
      (node (ref "POT3") (pin "1") (pinfunction "W0_1") (pintype "passive"))
    )
    (net (code "29") (name "/B10+") (class "Default")
      (node (ref "ADS3") (pin "8") (pinfunction "AIN2_8") (pintype "passive"))
      (node (ref "B10-R1") (pin "2") (pinfunction "2_2") (pintype "passive"))
      (node (ref "GAUGE10") (pin "3") (pinfunction "1_3") (pintype "passive"))
    )
    (net (code "30") (name "/B10-_P3W1") (class "Default")
      (node (ref "ADS3") (pin "9") (pinfunction "AIN3_9") (pintype "passive"))
      (node (ref "B10R3") (pin "1") (pinfunction "1_1") (pintype "passive"))
      (node (ref "GAUGE10") (pin "1") (pinfunction "1_1") (pintype "passive"))
      (node (ref "POT3") (pin "6") (pinfunction "W1_6") (pintype "passive"))
    )
    (net (code "31") (name "/B11+") (class "Default")
      (node (ref "ADS3") (pin "10") (pinfunction "AIN4_10") (pintype "passive"))
      (node (ref "B11-R1") (pin "2") (pinfunction "2_2") (pintype "passive"))
      (node (ref "GAUGE11") (pin "3") (pinfunction "1_3") (pintype "passive"))
    )
    (net (code "32") (name "/B11-_P3W2") (class "Default")
      (node (ref "ADS3") (pin "11") (pinfunction "AIN5_11") (pintype "passive"))
      (node (ref "B11R3") (pin "1") (pinfunction "1_1") (pintype "passive"))
      (node (ref "GAUGE11") (pin "1") (pinfunction "1_1") (pintype "passive"))
      (node (ref "POT3") (pin "13") (pinfunction "W2_13") (pintype "passive"))
    )
    (net (code "33") (name "/B12+") (class "Default")
      (node (ref "ADS3") (pin "12") (pinfunction "AIN6_12") (pintype "passive"))
      (node (ref "B12-R1") (pin "2") (pinfunction "2_2") (pintype "passive"))
      (node (ref "GAUGE12") (pin "3") (pinfunction "1_3") (pintype "passive"))
    )
    (net (code "34") (name "/B12-_P3W3") (class "Default")
      (node (ref "ADS3") (pin "13") (pinfunction "AIN7_13") (pintype "passive"))
      (node (ref "B12R3") (pin "1") (pinfunction "1_1") (pintype "passive"))
      (node (ref "GAUGE12") (pin "1") (pinfunction "1_1") (pintype "passive"))
      (node (ref "POT3") (pin "19") (pinfunction "W3_19") (pintype "passive"))
    )
    (net (code "35") (name "/CALIB_IN") (class "Default")
      (node (ref "ATMEGA328") (pin "32") (pinfunction "PD2(INT0)_32") (pintype "bidirectional"))
      (node (ref "CAL1") (pin "2") (pinfunction "DI_2") (pintype "bidirectional"))
    )
    (net (code "36") (name "/MEGA_XTAL1") (class "Default")
      (node (ref "ATMEGA328") (pin "7") (pinfunction "PB6(XTAL1/TOSC1)_7") (pintype "bidirectional"))
      (node (ref "CRYSTAL2-C1") (pin "2") (pinfunction "2_2") (pintype "passive"))
      (node (ref "MEGA_CRYSTAL") (pin "3") (pinfunction "2_3") (pintype "passive"))
    )
    (net (code "37") (name "/MEGA_XTAL2") (class "Default")
      (node (ref "ATMEGA328") (pin "8") (pinfunction "PB7(XTAL2/TOSC2)_8") (pintype "bidirectional"))
      (node (ref "CRYSTAL2-C2") (pin "2") (pinfunction "2_2") (pintype "passive"))
      (node (ref "MEGA_CRYSTAL") (pin "1") (pinfunction "1_1") (pintype "passive"))
    )
    (net (code "38") (name "/MISO") (class "Default")
      (node (ref "ADS1") (pin "22") (pinfunction "DOUT_22") (pintype "output"))
      (node (ref "ADS2") (pin "22") (pinfunction "DOUT_22") (pintype "output"))
      (node (ref "ADS3") (pin "22") (pinfunction "DOUT_22") (pintype "output"))
      (node (ref "ATMEGA328") (pin "16") (pinfunction "PB4(MISO)_16") (pintype "bidirectional"))
      (node (ref "ICSP") (pin "1") (pinfunction "1_1") (pintype "bidirectional"))
      (node (ref "SD_SLOT") (pin "DO") (pinfunction "DO_DO") (pintype "bidirectional"))
    )
    (net (code "39") (name "/MOSI") (class "Default")
      (node (ref "ADS1") (pin "23") (pinfunction "DIN_23") (pintype "input"))
      (node (ref "ADS2") (pin "23") (pinfunction "DIN_23") (pintype "input"))
      (node (ref "ADS3") (pin "23") (pinfunction "DIN_23") (pintype "input"))
      (node (ref "ATMEGA328") (pin "15") (pinfunction "PB3(MOSI/OC2)_15") (pintype "bidirectional"))
      (node (ref "ICSP") (pin "4") (pinfunction "4_4") (pintype "bidirectional"))
      (node (ref "SD_SLOT") (pin "DI") (pinfunction "DI_DI") (pintype "bidirectional"))
    )
    (net (code "40") (name "/P1B0") (class "Default")
      (node (ref "B1-R2") (pin "2") (pinfunction "2_2") (pintype "passive"))
      (node (ref "POT1") (pin "2") (pinfunction "B0_2") (pintype "passive"))
    )
    (net (code "41") (name "/P1B1") (class "Default")
      (node (ref "B2-R2") (pin "2") (pinfunction "2_2") (pintype "passive"))
      (node (ref "POT1") (pin "7") (pinfunction "B1_7") (pintype "passive"))
    )
    (net (code "42") (name "/P1B2") (class "Default")
      (node (ref "B3-R2") (pin "2") (pinfunction "2_2") (pintype "passive"))
      (node (ref "POT1") (pin "12") (pinfunction "B2_12") (pintype "passive"))
    )
    (net (code "43") (name "/P1B3") (class "Default")
      (node (ref "B4-R2") (pin "2") (pinfunction "2_2") (pintype "passive"))
      (node (ref "POT1") (pin "18") (pinfunction "B3_18") (pintype "passive"))
    )
    (net (code "44") (name "/P2B0") (class "Default")
      (node (ref "B5-R2") (pin "2") (pinfunction "2_2") (pintype "passive"))
      (node (ref "POT2") (pin "2") (pinfunction "B0_2") (pintype "passive"))
    )
    (net (code "45") (name "/P2B1") (class "Default")
      (node (ref "B6-R2") (pin "2") (pinfunction "2_2") (pintype "passive"))
      (node (ref "POT2") (pin "7") (pinfunction "B1_7") (pintype "passive"))
    )
    (net (code "46") (name "/P2B2") (class "Default")
      (node (ref "B7-R2") (pin "2") (pinfunction "2_2") (pintype "passive"))
      (node (ref "POT2") (pin "12") (pinfunction "B2_12") (pintype "passive"))
    )
    (net (code "47") (name "/P2B3") (class "Default")
      (node (ref "B8-R2") (pin "2") (pinfunction "2_2") (pintype "passive"))
      (node (ref "POT2") (pin "18") (pinfunction "B3_18") (pintype "passive"))
    )
    (net (code "48") (name "/P3B0") (class "Default")
      (node (ref "B9-R2") (pin "2") (pinfunction "2_2") (pintype "passive"))
      (node (ref "POT3") (pin "2") (pinfunction "B0_2") (pintype "passive"))
    )
    (net (code "49") (name "/P3B1") (class "Default")
      (node (ref "B10-R2") (pin "2") (pinfunction "2_2") (pintype "passive"))
      (node (ref "POT3") (pin "7") (pinfunction "B1_7") (pintype "passive"))
    )
    (net (code "50") (name "/P3B2") (class "Default")
      (node (ref "B11-R2") (pin "2") (pinfunction "2_2") (pintype "passive"))
      (node (ref "POT3") (pin "12") (pinfunction "B2_12") (pintype "passive"))
    )
    (net (code "51") (name "/P3B3") (class "Default")
      (node (ref "B12-R2") (pin "2") (pinfunction "2_2") (pintype "passive"))
      (node (ref "POT3") (pin "18") (pinfunction "B3_18") (pintype "passive"))
    )
    (net (code "52") (name "/POT_SELECT_0") (class "Default")
      (node (ref "ATMEGA328") (pin "9") (pinfunction "PD5(T1)_9") (pintype "bidirectional"))
      (node (ref "POT1") (pin "4") (pinfunction "AD0_4") (pintype "passive"))
      (node (ref "POT2") (pin "4") (pinfunction "AD0_4") (pintype "passive"))
      (node (ref "POT3") (pin "4") (pinfunction "AD0_4") (pintype "passive"))
    )
    (net (code "53") (name "/POT_SELECT_1") (class "Default")
      (node (ref "ATMEGA328") (pin "10") (pinfunction "PD6(AIN0)_10") (pintype "bidirectional"))
      (node (ref "POT1") (pin "16") (pinfunction "AD1_16") (pintype "passive"))
      (node (ref "POT2") (pin "16") (pinfunction "AD1_16") (pintype "passive"))
      (node (ref "POT3") (pin "16") (pinfunction "AD1_16") (pintype "passive"))
    )
    (net (code "54") (name "/RESET") (class "Default")
      (node (ref "ATMEGA328") (pin "29") (pinfunction "PC6(/RESET)_29") (pintype "bidirectional"))
      (node (ref "ICSP") (pin "5") (pinfunction "5_5") (pintype "bidirectional"))
      (node (ref "MEGA_RST") (pin "1") (pinfunction "1_1") (pintype "passive"))
    )
    (net (code "55") (name "/SCK") (class "Default")
      (node (ref "ADS1") (pin "24") (pinfunction "SCLK_24") (pintype "input"))
      (node (ref "ADS2") (pin "24") (pinfunction "SCLK_24") (pintype "input"))
      (node (ref "ADS3") (pin "24") (pinfunction "SCLK_24") (pintype "input"))
      (node (ref "ATMEGA328") (pin "17") (pinfunction "PB5(SCK)_17") (pintype "bidirectional"))
      (node (ref "ICSP") (pin "3") (pinfunction "3_3") (pintype "bidirectional"))
      (node (ref "SD_SLOT") (pin "SCLK") (pinfunction "SCK_SCLK") (pintype "bidirectional"))
    )
    (net (code "56") (name "/SCL") (class "Default")
      (node (ref "ATMEGA328") (pin "28") (pinfunction "PC5(ADC5/SCL)_28") (pintype "bidirectional"))
      (node (ref "POT1") (pin "14") (pinfunction "SCL_14") (pintype "passive"))
      (node (ref "POT2") (pin "14") (pinfunction "SCL_14") (pintype "passive"))
      (node (ref "POT3") (pin "14") (pinfunction "SCL_14") (pintype "passive"))
      (node (ref "RTC") (pin "6") (pinfunction "SCL_6") (pintype "bidirectional"))
      (node (ref "SCL_PULL") (pin "1") (pinfunction "1_1") (pintype "passive"))
    )
    (net (code "57") (name "/SDA") (class "Default")
      (node (ref "ATMEGA328") (pin "27") (pinfunction "PC4(ADC4/SDA)_27") (pintype "bidirectional"))
      (node (ref "POT1") (pin "9") (pinfunction "SDA_9") (pintype "passive"))
      (node (ref "POT2") (pin "9") (pinfunction "SDA_9") (pintype "passive"))
      (node (ref "POT3") (pin "9") (pinfunction "SDA_9") (pintype "passive"))
      (node (ref "RTC") (pin "5") (pinfunction "SDA_5") (pintype "bidirectional"))
      (node (ref "SDA_PULL") (pin "1") (pinfunction "1_1") (pintype "passive"))
    )
    (net (code "58") (name "/SD_CS") (class "Default")
      (node (ref "ATMEGA328") (pin "31") (pinfunction "PD1(TXD)_31") (pintype "bidirectional"))
      (node (ref "SD_SLOT") (pin "CS") (pinfunction "~{CS}_CS") (pintype "bidirectional"))
    )
    (net (code "59") (name "/SQW") (class "Default")
      (node (ref "ATMEGA328") (pin "30") (pinfunction "PD0(RXD)_30") (pintype "bidirectional"))
      (node (ref "RTC") (pin "7") (pinfunction "SQW_7") (pintype "bidirectional"))
    )
    (net (code "60") (name "/VREF") (class "Default")
      (node (ref "ADS1") (pin "4") (pinfunction "VREFP_4") (pintype "passive"))
      (node (ref "ADS2") (pin "4") (pinfunction "VREFP_4") (pintype "passive"))
      (node (ref "ADS3") (pin "4") (pinfunction "VREFP_4") (pintype "passive"))
      (node (ref "VREF-R1") (pin "1") (pinfunction "1_1") (pintype "passive"))
      (node (ref "VREF_C1") (pin "1") (pinfunction "1_1") (pintype "passive"))
      (node (ref "VREF_R2") (pin "2") (pinfunction "2_2") (pintype "passive"))
    )
    (net (code "61") (name "/WP") (class "Default")
      (node (ref "ATMEGA328") (pin "11") (pinfunction "PD7(AIN1)_11") (pintype "bidirectional"))
      (node (ref "P1_WP") (pin "2") (pinfunction "2_2") (pintype "passive"))
      (node (ref "P2_WP") (pin "2") (pinfunction "2_2") (pintype "passive"))
      (node (ref "P3_WP") (pin "2") (pinfunction "2_2") (pintype "passive"))
      (node (ref "POT1") (pin "5") (pinfunction "~_5") (pintype "passive"))
      (node (ref "POT2") (pin "5") (pinfunction "~_5") (pintype "passive"))
      (node (ref "POT3") (pin "5") (pinfunction "~_5") (pintype "passive"))
    )
    (net (code "62") (name "/XTAL1") (class "Default")
      (node (ref "ADS1") (pin "19") (pinfunction "XTAL1/CLKIN_19") (pintype "input"))
      (node (ref "ADS2") (pin "19") (pinfunction "XTAL1/CLKIN_19") (pintype "input"))
      (node (ref "ADS3") (pin "19") (pinfunction "XTAL1/CLKIN_19") (pintype "input"))
      (node (ref "ADS_CRYSTAL") (pin "1") (pinfunction "1_1") (pintype "passive"))
      (node (ref "CRYSTAL1-C1") (pin "1") (pinfunction "1_1") (pintype "passive"))
    )
    (net (code "63") (name "/XTAL2") (class "Default")
      (node (ref "ADS1") (pin "18") (pinfunction "XTAL2_18") (pintype "passive"))
      (node (ref "ADS2") (pin "18") (pinfunction "XTAL2_18") (pintype "passive"))
      (node (ref "ADS3") (pin "18") (pinfunction "XTAL2_18") (pintype "passive"))
      (node (ref "ADS_CRYSTAL") (pin "3") (pinfunction "2_3") (pintype "passive"))
      (node (ref "CRYSTAL1-C2") (pin "1") (pinfunction "1_1") (pintype "passive"))
    )
    (net (code "64") (name "AGND") (class "Default")
      (node (ref "5V-DCPL") (pin "2") (pinfunction "2_2") (pintype "passive"))
      (node (ref "5V-R2") (pin "1") (pinfunction "1_1") (pintype "passive"))
      (node (ref "6V-R2") (pin "1") (pinfunction "1_1") (pintype "passive"))
      (node (ref "ADS1") (pin "17") (pinfunction "DGND_17") (pintype "power_in"))
      (node (ref "ADS1") (pin "2") (pinfunction "AGND_2") (pintype "passive"))
      (node (ref "ADS1") (pin "3") (pinfunction "VREFN_3") (pintype "passive"))
      (node (ref "ADS1-DCPL1") (pin "2") (pinfunction "2_2") (pintype "passive"))
      (node (ref "ADS1-DCPL2") (pin "2") (pinfunction "2_2") (pintype "passive"))
      (node (ref "ADS2") (pin "17") (pinfunction "DGND_17") (pintype "power_in"))
      (node (ref "ADS2") (pin "2") (pinfunction "AGND_2") (pintype "passive"))
      (node (ref "ADS2") (pin "3") (pinfunction "VREFN_3") (pintype "passive"))
      (node (ref "ADS2-DCPL1") (pin "2") (pinfunction "2_2") (pintype "passive"))
      (node (ref "ADS2-DCPL2") (pin "2") (pinfunction "2_2") (pintype "passive"))
      (node (ref "ADS3") (pin "17") (pinfunction "DGND_17") (pintype "power_in"))
      (node (ref "ADS3") (pin "2") (pinfunction "AGND_2") (pintype "passive"))
      (node (ref "ADS3") (pin "3") (pinfunction "VREFN_3") (pintype "passive"))
      (node (ref "ADS3-DCPL1") (pin "2") (pinfunction "2_2") (pintype "passive"))
      (node (ref "ADS3-DCPL2") (pin "2") (pinfunction "2_2") (pintype "passive"))
      (node (ref "ATMEGA328") (pin "21") (pinfunction "AGND_21") (pintype "bidirectional"))
      (node (ref "ATMEGA328") (pin "3") (pinfunction "GND_3") (pintype "bidirectional"))
      (node (ref "ATMEGA328") (pin "5") (pinfunction "GND_5") (pintype "bidirectional"))
      (node (ref "B1-R1") (pin "1") (pinfunction "1_1") (pintype "passive"))
      (node (ref "B10-R1") (pin "1") (pinfunction "1_1") (pintype "passive"))
      (node (ref "B11-R1") (pin "1") (pinfunction "1_1") (pintype "passive"))
      (node (ref "B12-R1") (pin "1") (pinfunction "1_1") (pintype "passive"))
      (node (ref "B2-R1") (pin "1") (pinfunction "1_1") (pintype "passive"))
      (node (ref "B3-R1") (pin "1") (pinfunction "1_1") (pintype "passive"))
      (node (ref "B4-R1") (pin "1") (pinfunction "1_1") (pintype "passive"))
      (node (ref "B5-R1") (pin "1") (pinfunction "1_1") (pintype "passive"))
      (node (ref "B6-R1") (pin "1") (pinfunction "1_1") (pintype "passive"))
      (node (ref "B7-R1") (pin "1") (pinfunction "1_1") (pintype "passive"))
      (node (ref "B8-R1") (pin "1") (pinfunction "1_1") (pintype "passive"))
      (node (ref "B9-R1") (pin "1") (pinfunction "1_1") (pintype "passive"))
      (node (ref "BT1") (pin "GND") (pinfunction "-_GND") (pintype "power_in"))
      (node (ref "CAL1") (pin "6") (pinfunction "VSS_6") (pintype "bidirectional"))
      (node (ref "CAL10") (pin "6") (pinfunction "VSS_6") (pintype "bidirectional"))
      (node (ref "CAL11") (pin "6") (pinfunction "VSS_6") (pintype "bidirectional"))
      (node (ref "CAL12") (pin "6") (pinfunction "VSS_6") (pintype "bidirectional"))
      (node (ref "CAL2") (pin "6") (pinfunction "VSS_6") (pintype "bidirectional"))
      (node (ref "CAL3") (pin "6") (pinfunction "VSS_6") (pintype "bidirectional"))
      (node (ref "CAL4") (pin "6") (pinfunction "VSS_6") (pintype "bidirectional"))
      (node (ref "CAL5") (pin "6") (pinfunction "VSS_6") (pintype "bidirectional"))
      (node (ref "CAL6") (pin "6") (pinfunction "VSS_6") (pintype "bidirectional"))
      (node (ref "CAL7") (pin "6") (pinfunction "VSS_6") (pintype "bidirectional"))
      (node (ref "CAL8") (pin "6") (pinfunction "VSS_6") (pintype "bidirectional"))
      (node (ref "CAL9") (pin "6") (pinfunction "VSS_6") (pintype "bidirectional"))
      (node (ref "CRYSTAL1-C1") (pin "2") (pinfunction "2_2") (pintype "passive"))
      (node (ref "CRYSTAL1-C2") (pin "2") (pinfunction "2_2") (pintype "passive"))
      (node (ref "CRYSTAL2-C1") (pin "1") (pinfunction "1_1") (pintype "passive"))
      (node (ref "CRYSTAL2-C2") (pin "1") (pinfunction "1_1") (pintype "passive"))
      (node (ref "GAUGE-DCPL") (pin "2") (pinfunction "2_2") (pintype "passive"))
      (node (ref "GAUGE1") (pin "2") (pinfunction "1_2") (pintype "passive"))
      (node (ref "GAUGE10") (pin "2") (pinfunction "1_2") (pintype "passive"))
      (node (ref "GAUGE11") (pin "2") (pinfunction "1_2") (pintype "passive"))
      (node (ref "GAUGE12") (pin "2") (pinfunction "1_2") (pintype "passive"))
      (node (ref "GAUGE2") (pin "2") (pinfunction "1_2") (pintype "passive"))
      (node (ref "GAUGE3") (pin "2") (pinfunction "1_2") (pintype "passive"))
      (node (ref "GAUGE4") (pin "2") (pinfunction "1_2") (pintype "passive"))
      (node (ref "GAUGE5") (pin "2") (pinfunction "1_2") (pintype "passive"))
      (node (ref "GAUGE6") (pin "2") (pinfunction "1_2") (pintype "passive"))
      (node (ref "GAUGE7") (pin "2") (pinfunction "1_2") (pintype "passive"))
      (node (ref "GAUGE8") (pin "2") (pinfunction "1_2") (pintype "passive"))
      (node (ref "GAUGE9") (pin "2") (pinfunction "1_2") (pintype "passive"))
      (node (ref "ICSP") (pin "6") (pinfunction "6_6") (pintype "bidirectional"))
      (node (ref "MEGA-DCPL") (pin "2") (pinfunction "2_2") (pintype "passive"))
      (node (ref "POT1") (pin "10") (pinfunction "VSS_10") (pintype "power_in"))
      (node (ref "POT1") (pin "15") (pinfunction "DGND_15") (pintype "passive"))
      (node (ref "POT1-DCPL") (pin "2") (pinfunction "2_2") (pintype "passive"))
      (node (ref "POT2") (pin "10") (pinfunction "VSS_10") (pintype "power_in"))
      (node (ref "POT2") (pin "15") (pinfunction "DGND_15") (pintype "passive"))
      (node (ref "POT2-DCPL") (pin "2") (pinfunction "2_2") (pintype "passive"))
      (node (ref "POT3") (pin "10") (pinfunction "VSS_10") (pintype "power_in"))
      (node (ref "POT3") (pin "15") (pinfunction "DGND_15") (pintype "passive"))
      (node (ref "POT3-DCPL") (pin "2") (pinfunction "2_2") (pintype "passive"))
      (node (ref "PROG-DCPL") (pin "2") (pinfunction "2_2") (pintype "passive"))
      (node (ref "PWR-DCPL1") (pin "2") (pinfunction "2_2") (pintype "passive"))
      (node (ref "PWR-DCPL2") (pin "2") (pinfunction "2_2") (pintype "passive"))
      (node (ref "PWR-IN") (pin "2") (pinfunction "1_2") (pintype "passive"))
      (node (ref "PWR-IN") (pin "3") (pinfunction "1_3") (pintype "passive"))
      (node (ref "RTC") (pin "4") (pinfunction "GND_4") (pintype "bidirectional"))
      (node (ref "RTC_DCPL") (pin "2") (pinfunction "2_2") (pintype "passive"))
      (node (ref "SD-DCPL") (pin "2") (pinfunction "2_2") (pintype "passive"))
      (node (ref "SD_SLOT") (pin "CD1") (pinfunction "CD1_CD1") (pintype "bidirectional"))
      (node (ref "SD_SLOT") (pin "CD2") (pinfunction "CD2_CD2") (pintype "bidirectional"))
      (node (ref "SD_SLOT") (pin "GND") (pinfunction "GND_GND") (pintype "bidirectional"))
      (node (ref "SD_SLOT") (pin "GND1") (pinfunction "SHIELD_GND1") (pintype "bidirectional"))
      (node (ref "SD_SLOT") (pin "GND3") (pinfunction "SHIELD_GND3") (pintype "bidirectional"))
      (node (ref "VREF_C1") (pin "2") (pinfunction "2_2") (pintype "passive"))
      (node (ref "VREF_R2") (pin "1") (pinfunction "1_1") (pintype "passive"))
    )
    (net (code "65") (name "Net-(+5V-ADJ)") (class "Default")
      (node (ref "+5V") (pin "1") (pinfunction "ADJ_1") (pintype "input"))
      (node (ref "5V-R1") (pin "1") (pinfunction "1_1") (pintype "passive"))
      (node (ref "5V-R2") (pin "2") (pinfunction "2_2") (pintype "passive"))
    )
    (net (code "66") (name "Net-(CAL1-DO)") (class "Default")
      (node (ref "CAL1") (pin "1") (pinfunction "DO_1") (pintype "bidirectional"))
      (node (ref "CAL2") (pin "2") (pinfunction "DI_2") (pintype "bidirectional"))
    )
    (net (code "67") (name "Net-(CAL2-DO)") (class "Default")
      (node (ref "CAL2") (pin "1") (pinfunction "DO_1") (pintype "bidirectional"))
      (node (ref "CAL3") (pin "2") (pinfunction "DI_2") (pintype "bidirectional"))
    )
    (net (code "68") (name "Net-(CAL3-DO)") (class "Default")
      (node (ref "CAL3") (pin "1") (pinfunction "DO_1") (pintype "bidirectional"))
      (node (ref "CAL4") (pin "2") (pinfunction "DI_2") (pintype "bidirectional"))
    )
    (net (code "69") (name "Net-(CAL4-DO)") (class "Default")
      (node (ref "CAL4") (pin "1") (pinfunction "DO_1") (pintype "bidirectional"))
      (node (ref "CAL5") (pin "2") (pinfunction "DI_2") (pintype "bidirectional"))
    )
    (net (code "70") (name "Net-(CAL5-DO)") (class "Default")
      (node (ref "CAL5") (pin "1") (pinfunction "DO_1") (pintype "bidirectional"))
      (node (ref "CAL6") (pin "2") (pinfunction "DI_2") (pintype "bidirectional"))
    )
    (net (code "71") (name "Net-(CAL6-DO)") (class "Default")
      (node (ref "CAL6") (pin "1") (pinfunction "DO_1") (pintype "bidirectional"))
      (node (ref "CAL7") (pin "2") (pinfunction "DI_2") (pintype "bidirectional"))
    )
    (net (code "72") (name "Net-(CAL7-DO)") (class "Default")
      (node (ref "CAL7") (pin "1") (pinfunction "DO_1") (pintype "bidirectional"))
      (node (ref "CAL8") (pin "2") (pinfunction "DI_2") (pintype "bidirectional"))
    )
    (net (code "73") (name "Net-(CAL8-DO)") (class "Default")
      (node (ref "CAL8") (pin "1") (pinfunction "DO_1") (pintype "bidirectional"))
      (node (ref "CAL9") (pin "2") (pinfunction "DI_2") (pintype "bidirectional"))
    )
    (net (code "74") (name "Net-(CAL10-DI)") (class "Default")
      (node (ref "CAL10") (pin "2") (pinfunction "DI_2") (pintype "bidirectional"))
      (node (ref "CAL9") (pin "1") (pinfunction "DO_1") (pintype "bidirectional"))
    )
    (net (code "75") (name "Net-(CAL10-DO)") (class "Default")
      (node (ref "CAL10") (pin "1") (pinfunction "DO_1") (pintype "bidirectional"))
      (node (ref "CAL11") (pin "2") (pinfunction "DI_2") (pintype "bidirectional"))
    )
    (net (code "76") (name "Net-(CAL11-DO)") (class "Default")
      (node (ref "CAL11") (pin "1") (pinfunction "DO_1") (pintype "bidirectional"))
      (node (ref "CAL12") (pin "2") (pinfunction "DI_2") (pintype "bidirectional"))
    )
    (net (code "77") (name "Net-(GAUGE-ADJ)") (class "Default")
      (node (ref "6V-R1") (pin "1") (pinfunction "1_1") (pintype "passive"))
      (node (ref "6V-R2") (pin "2") (pinfunction "2_2") (pintype "passive"))
      (node (ref "GAUGE") (pin "1") (pinfunction "ADJ_1") (pintype "input"))
    )
    (net (code "78") (name "Net-(RTC-X1)") (class "Default")
      (node (ref "RTC") (pin "1") (pinfunction "X1_1") (pintype "bidirectional"))
      (node (ref "RTC_CRYSTAL") (pin "P$2") (pinfunction "2_P$2") (pintype "passive"))
    )
    (net (code "79") (name "Net-(RTC-X2)") (class "Default")
      (node (ref "RTC") (pin "2") (pinfunction "X2_2") (pintype "bidirectional"))
      (node (ref "RTC_CRYSTAL") (pin "P$1") (pinfunction "1_P$1") (pintype "passive"))
    )
    (net (code "80") (name "V+") (class "Default")
      (node (ref "6V-R1") (pin "2") (pinfunction "2_2") (pintype "passive"))
      (node (ref "B1-R2") (pin "1") (pinfunction "1_1") (pintype "passive"))
      (node (ref "B10-R2") (pin "1") (pinfunction "1_1") (pintype "passive"))
      (node (ref "B10R3") (pin "2") (pinfunction "2_2") (pintype "passive"))
      (node (ref "B11-R2") (pin "1") (pinfunction "1_1") (pintype "passive"))
      (node (ref "B11R3") (pin "2") (pinfunction "2_2") (pintype "passive"))
      (node (ref "B12-R2") (pin "1") (pinfunction "1_1") (pintype "passive"))
      (node (ref "B12R3") (pin "2") (pinfunction "2_2") (pintype "passive"))
      (node (ref "B1R3") (pin "2") (pinfunction "2_2") (pintype "passive"))
      (node (ref "B2-R2") (pin "1") (pinfunction "1_1") (pintype "passive"))
      (node (ref "B2R3") (pin "2") (pinfunction "2_2") (pintype "passive"))
      (node (ref "B3-R2") (pin "1") (pinfunction "1_1") (pintype "passive"))
      (node (ref "B3R3") (pin "2") (pinfunction "2_2") (pintype "passive"))
      (node (ref "B4-R2") (pin "1") (pinfunction "1_1") (pintype "passive"))
      (node (ref "B4R3") (pin "2") (pinfunction "2_2") (pintype "passive"))
      (node (ref "B5-R2") (pin "1") (pinfunction "1_1") (pintype "passive"))
      (node (ref "B5R3") (pin "2") (pinfunction "2_2") (pintype "passive"))
      (node (ref "B6-R2") (pin "1") (pinfunction "1_1") (pintype "passive"))
      (node (ref "B6R3") (pin "2") (pinfunction "2_2") (pintype "passive"))
      (node (ref "B7-R2") (pin "1") (pinfunction "1_1") (pintype "passive"))
      (node (ref "B7R3") (pin "2") (pinfunction "2_2") (pintype "passive"))
      (node (ref "B8-R2") (pin "1") (pinfunction "1_1") (pintype "passive"))
      (node (ref "B8R3") (pin "2") (pinfunction "2_2") (pintype "passive"))
      (node (ref "B9-R2") (pin "1") (pinfunction "1_1") (pintype "passive"))
      (node (ref "B9R3") (pin "2") (pinfunction "2_2") (pintype "passive"))
      (node (ref "GAUGE") (pin "2") (pinfunction "OUT_2") (pintype "output"))
      (node (ref "GAUGE-DCPL") (pin "1") (pinfunction "1_1") (pintype "passive"))
      (node (ref "GAUGE1") (pin "4") (pinfunction "1_4") (pintype "passive"))
      (node (ref "GAUGE10") (pin "4") (pinfunction "1_4") (pintype "passive"))
      (node (ref "GAUGE11") (pin "4") (pinfunction "1_4") (pintype "passive"))
      (node (ref "GAUGE12") (pin "4") (pinfunction "1_4") (pintype "passive"))
      (node (ref "GAUGE2") (pin "4") (pinfunction "1_4") (pintype "passive"))
      (node (ref "GAUGE3") (pin "4") (pinfunction "1_4") (pintype "passive"))
      (node (ref "GAUGE4") (pin "4") (pinfunction "1_4") (pintype "passive"))
      (node (ref "GAUGE5") (pin "4") (pinfunction "1_4") (pintype "passive"))
      (node (ref "GAUGE6") (pin "4") (pinfunction "1_4") (pintype "passive"))
      (node (ref "GAUGE7") (pin "4") (pinfunction "1_4") (pintype "passive"))
      (node (ref "GAUGE8") (pin "4") (pinfunction "1_4") (pintype "passive"))
      (node (ref "GAUGE9") (pin "4") (pinfunction "1_4") (pintype "passive"))
    )
    (net (code "81") (name "unconnected-(ADS1A-D0{slash}CLKOUT-Pad25)") (class "Default")
      (node (ref "ADS1") (pin "25") (pinfunction "D0/CLKOUT_25") (pintype "passive"))
    )
    (net (code "82") (name "unconnected-(ADS1A-D1-Pad26)") (class "Default")
      (node (ref "ADS1") (pin "26") (pinfunction "D1_26") (pintype "passive"))
    )
    (net (code "83") (name "unconnected-(ADS1A-D2-Pad27)") (class "Default")
      (node (ref "ADS1") (pin "27") (pinfunction "D2_27") (pintype "passive"))
    )
    (net (code "84") (name "unconnected-(ADS1A-D3-Pad28)") (class "Default")
      (node (ref "ADS1") (pin "28") (pinfunction "D3_28") (pintype "passive"))
    )
    (net (code "85") (name "unconnected-(ADS2A-D0{slash}CLKOUT-Pad25)") (class "Default")
      (node (ref "ADS2") (pin "25") (pinfunction "D0/CLKOUT_25") (pintype "passive"))
    )
    (net (code "86") (name "unconnected-(ADS2A-D1-Pad26)") (class "Default")
      (node (ref "ADS2") (pin "26") (pinfunction "D1_26") (pintype "passive"))
    )
    (net (code "87") (name "unconnected-(ADS2A-D2-Pad27)") (class "Default")
      (node (ref "ADS2") (pin "27") (pinfunction "D2_27") (pintype "passive"))
    )
    (net (code "88") (name "unconnected-(ADS2A-D3-Pad28)") (class "Default")
      (node (ref "ADS2") (pin "28") (pinfunction "D3_28") (pintype "passive"))
    )
    (net (code "89") (name "unconnected-(ADS3A-D0{slash}CLKOUT-Pad25)") (class "Default")
      (node (ref "ADS3") (pin "25") (pinfunction "D0/CLKOUT_25") (pintype "passive"))
    )
    (net (code "90") (name "unconnected-(ADS3A-D1-Pad26)") (class "Default")
      (node (ref "ADS3") (pin "26") (pinfunction "D1_26") (pintype "passive"))
    )
    (net (code "91") (name "unconnected-(ADS3A-D2-Pad27)") (class "Default")
      (node (ref "ADS3") (pin "27") (pinfunction "D2_27") (pintype "passive"))
    )
    (net (code "92") (name "unconnected-(ADS3A-D3-Pad28)") (class "Default")
      (node (ref "ADS3") (pin "28") (pinfunction "D3_28") (pintype "passive"))
    )
    (net (code "93") (name "unconnected-(ATMEGA328-ADC6-Pad19)") (class "Default")
      (node (ref "ATMEGA328") (pin "19") (pinfunction "ADC6_19") (pintype "bidirectional"))
    )
    (net (code "94") (name "unconnected-(ATMEGA328-ADC7-Pad22)") (class "Default")
      (node (ref "ATMEGA328") (pin "22") (pinfunction "ADC7_22") (pintype "bidirectional"))
    )
    (net (code "95") (name "unconnected-(ATMEGA328-AREF-Pad20)") (class "Default")
      (node (ref "ATMEGA328") (pin "20") (pinfunction "AREF_20") (pintype "bidirectional"))
    )
    (net (code "96") (name "unconnected-(ATMEGA328-PC0(ADC0)-Pad23)") (class "Default")
      (node (ref "ATMEGA328") (pin "23") (pinfunction "PC0(ADC0)_23") (pintype "bidirectional"))
    )
    (net (code "97") (name "unconnected-(ATMEGA328-PC1(ADC1)-Pad24)") (class "Default")
      (node (ref "ATMEGA328") (pin "24") (pinfunction "PC1(ADC1)_24") (pintype "bidirectional"))
    )
    (net (code "98") (name "unconnected-(ATMEGA328-PC2(ADC2)-Pad25)") (class "Default")
      (node (ref "ATMEGA328") (pin "25") (pinfunction "PC2(ADC2)_25") (pintype "bidirectional"))
    )
    (net (code "99") (name "unconnected-(ATMEGA328-PC3(ADC3)-Pad26)") (class "Default")
      (node (ref "ATMEGA328") (pin "26") (pinfunction "PC3(ADC3)_26") (pintype "bidirectional"))
    )
    (net (code "100") (name "unconnected-(CAL12-DO-Pad1)") (class "Default")
      (node (ref "CAL12") (pin "1") (pinfunction "DO_1") (pintype "bidirectional"))
    )
    (net (code "101") (name "unconnected-(POT1-A0-Pad3)") (class "Default")
      (node (ref "POT1") (pin "3") (pinfunction "A0_3") (pintype "passive"))
    )
    (net (code "102") (name "unconnected-(POT1-A1-Pad8)") (class "Default")
      (node (ref "POT1") (pin "8") (pinfunction "A1_8") (pintype "passive"))
    )
    (net (code "103") (name "unconnected-(POT1-A2-Pad11)") (class "Default")
      (node (ref "POT1") (pin "11") (pinfunction "A2_11") (pintype "passive"))
    )
    (net (code "104") (name "unconnected-(POT1-A3-Pad17)") (class "Default")
      (node (ref "POT1") (pin "17") (pinfunction "A3_17") (pintype "passive"))
    )
    (net (code "105") (name "unconnected-(POT2-A0-Pad3)") (class "Default")
      (node (ref "POT2") (pin "3") (pinfunction "A0_3") (pintype "passive"))
    )
    (net (code "106") (name "unconnected-(POT2-A1-Pad8)") (class "Default")
      (node (ref "POT2") (pin "8") (pinfunction "A1_8") (pintype "passive"))
    )
    (net (code "107") (name "unconnected-(POT2-A2-Pad11)") (class "Default")
      (node (ref "POT2") (pin "11") (pinfunction "A2_11") (pintype "passive"))
    )
    (net (code "108") (name "unconnected-(POT2-A3-Pad17)") (class "Default")
      (node (ref "POT2") (pin "17") (pinfunction "A3_17") (pintype "passive"))
    )
    (net (code "109") (name "unconnected-(POT3-A0-Pad3)") (class "Default")
      (node (ref "POT3") (pin "3") (pinfunction "A0_3") (pintype "passive"))
    )
    (net (code "110") (name "unconnected-(POT3-A1-Pad8)") (class "Default")
      (node (ref "POT3") (pin "8") (pinfunction "A1_8") (pintype "passive"))
    )
    (net (code "111") (name "unconnected-(POT3-A2-Pad11)") (class "Default")
      (node (ref "POT3") (pin "11") (pinfunction "A2_11") (pintype "passive"))
    )
    (net (code "112") (name "unconnected-(POT3-A3-Pad17)") (class "Default")
      (node (ref "POT3") (pin "17") (pinfunction "A3_17") (pintype "passive"))
    )
    (net (code "113") (name "unconnected-(SD_SLOT-RSV-PadRSV1)") (class "Default")
      (node (ref "SD_SLOT") (pin "RSV1") (pinfunction "RSV_RSV1") (pintype "bidirectional"))
    )
    (net (code "114") (name "unconnected-(SD_SLOT-RSV-PadRSV2)") (class "Default")
      (node (ref "SD_SLOT") (pin "RSV2") (pinfunction "RSV_RSV2") (pintype "bidirectional"))
    )
  )
)
